# io-board-f-9.net
KiCad netlist of a schematic drawn in EAGLE
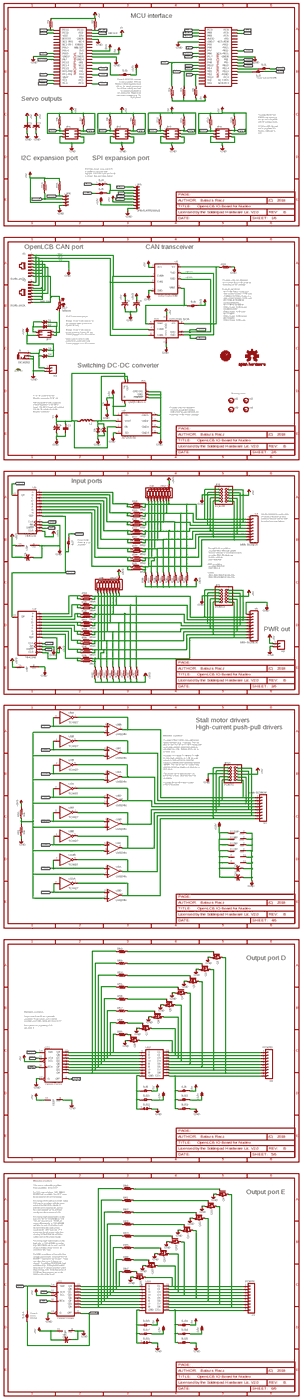
[diagram p0: schematic, sheet 1, overview]
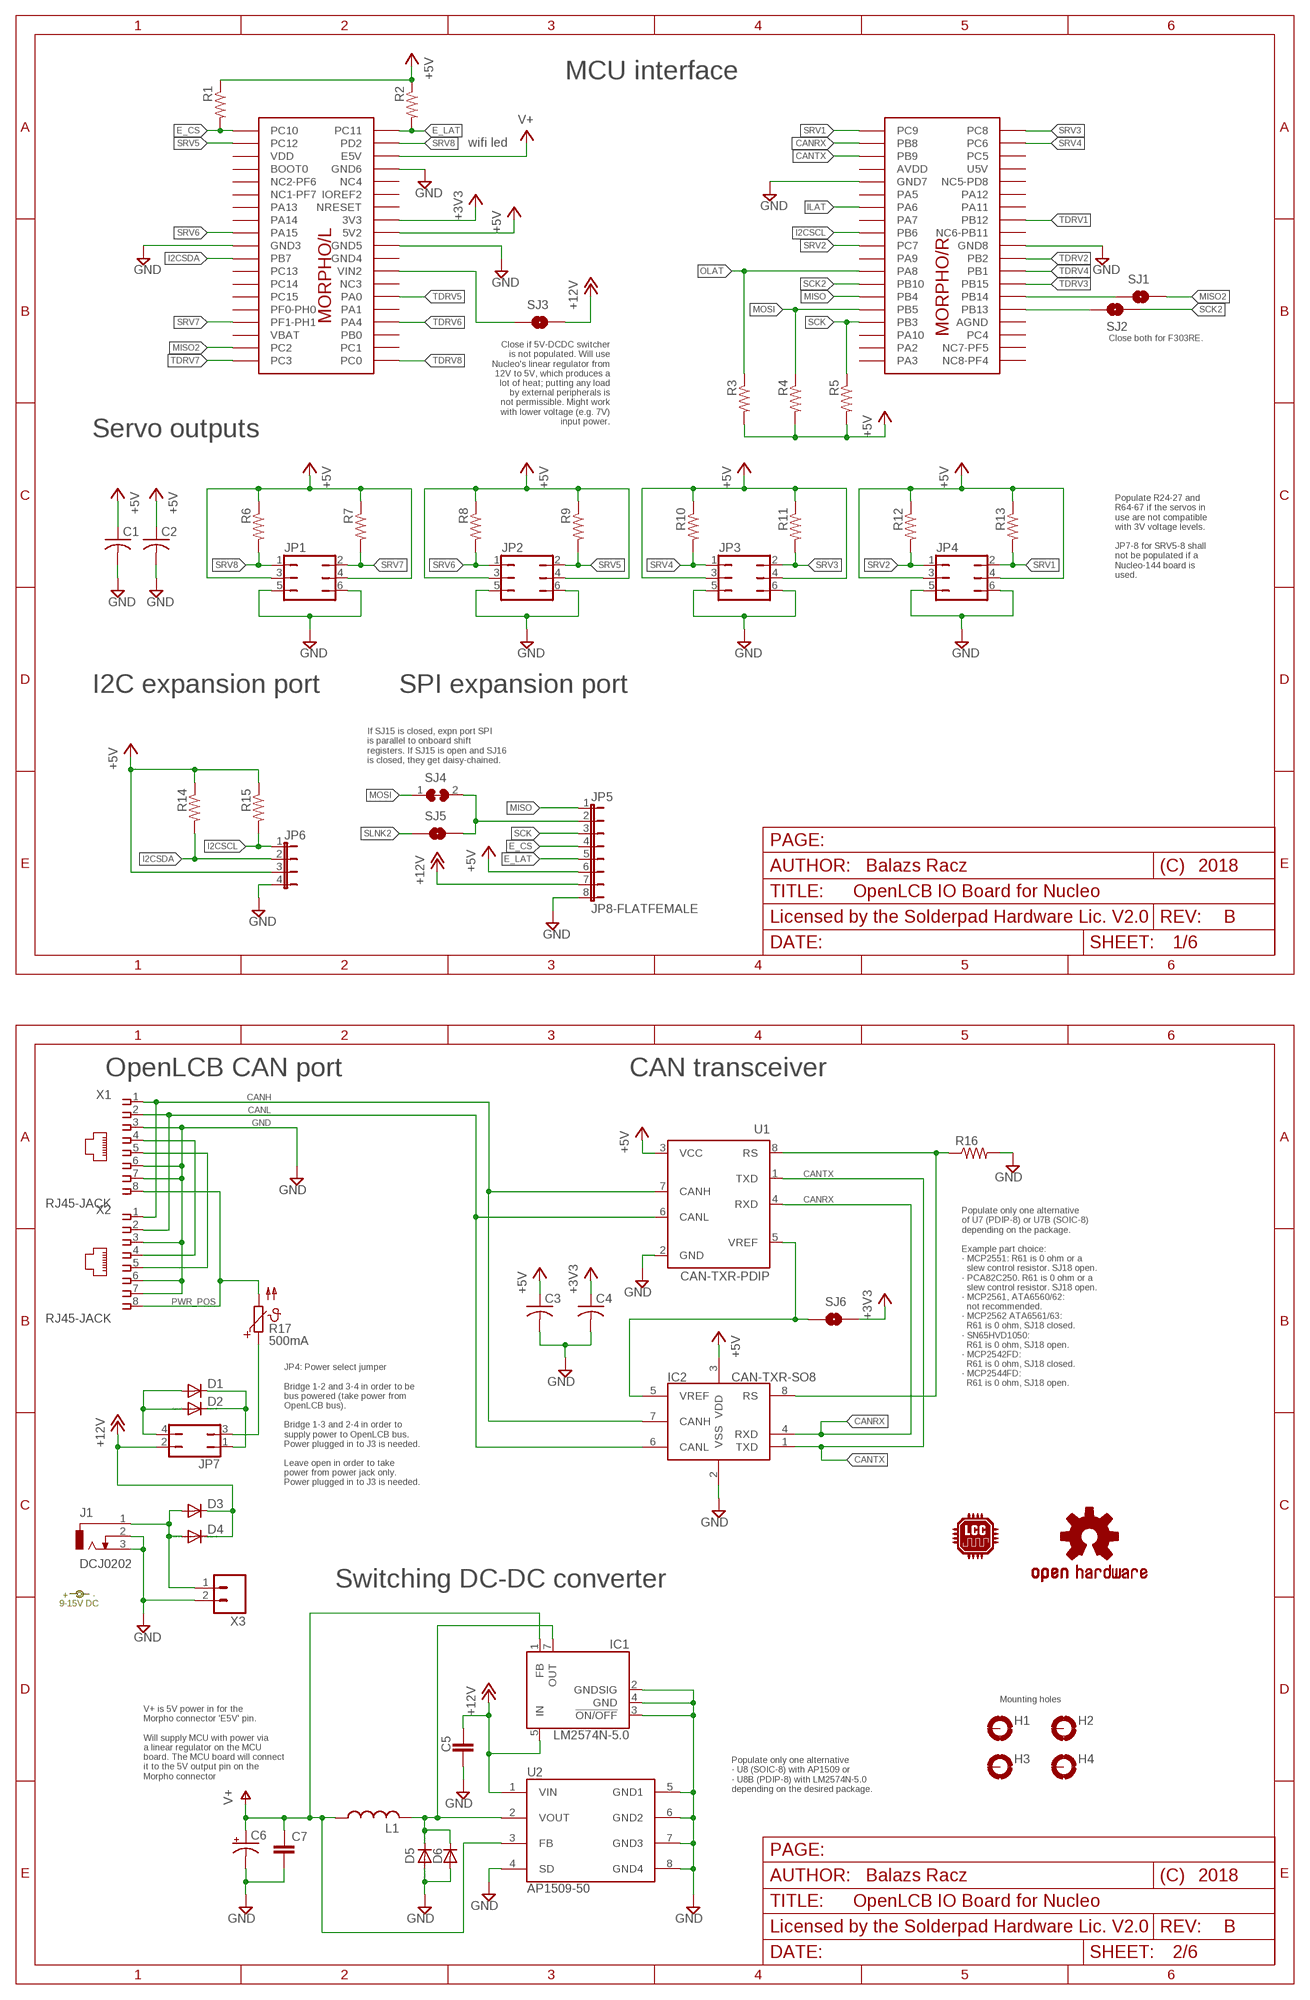
[diagram p1: schematic, sheet 1, part 1 of 4]
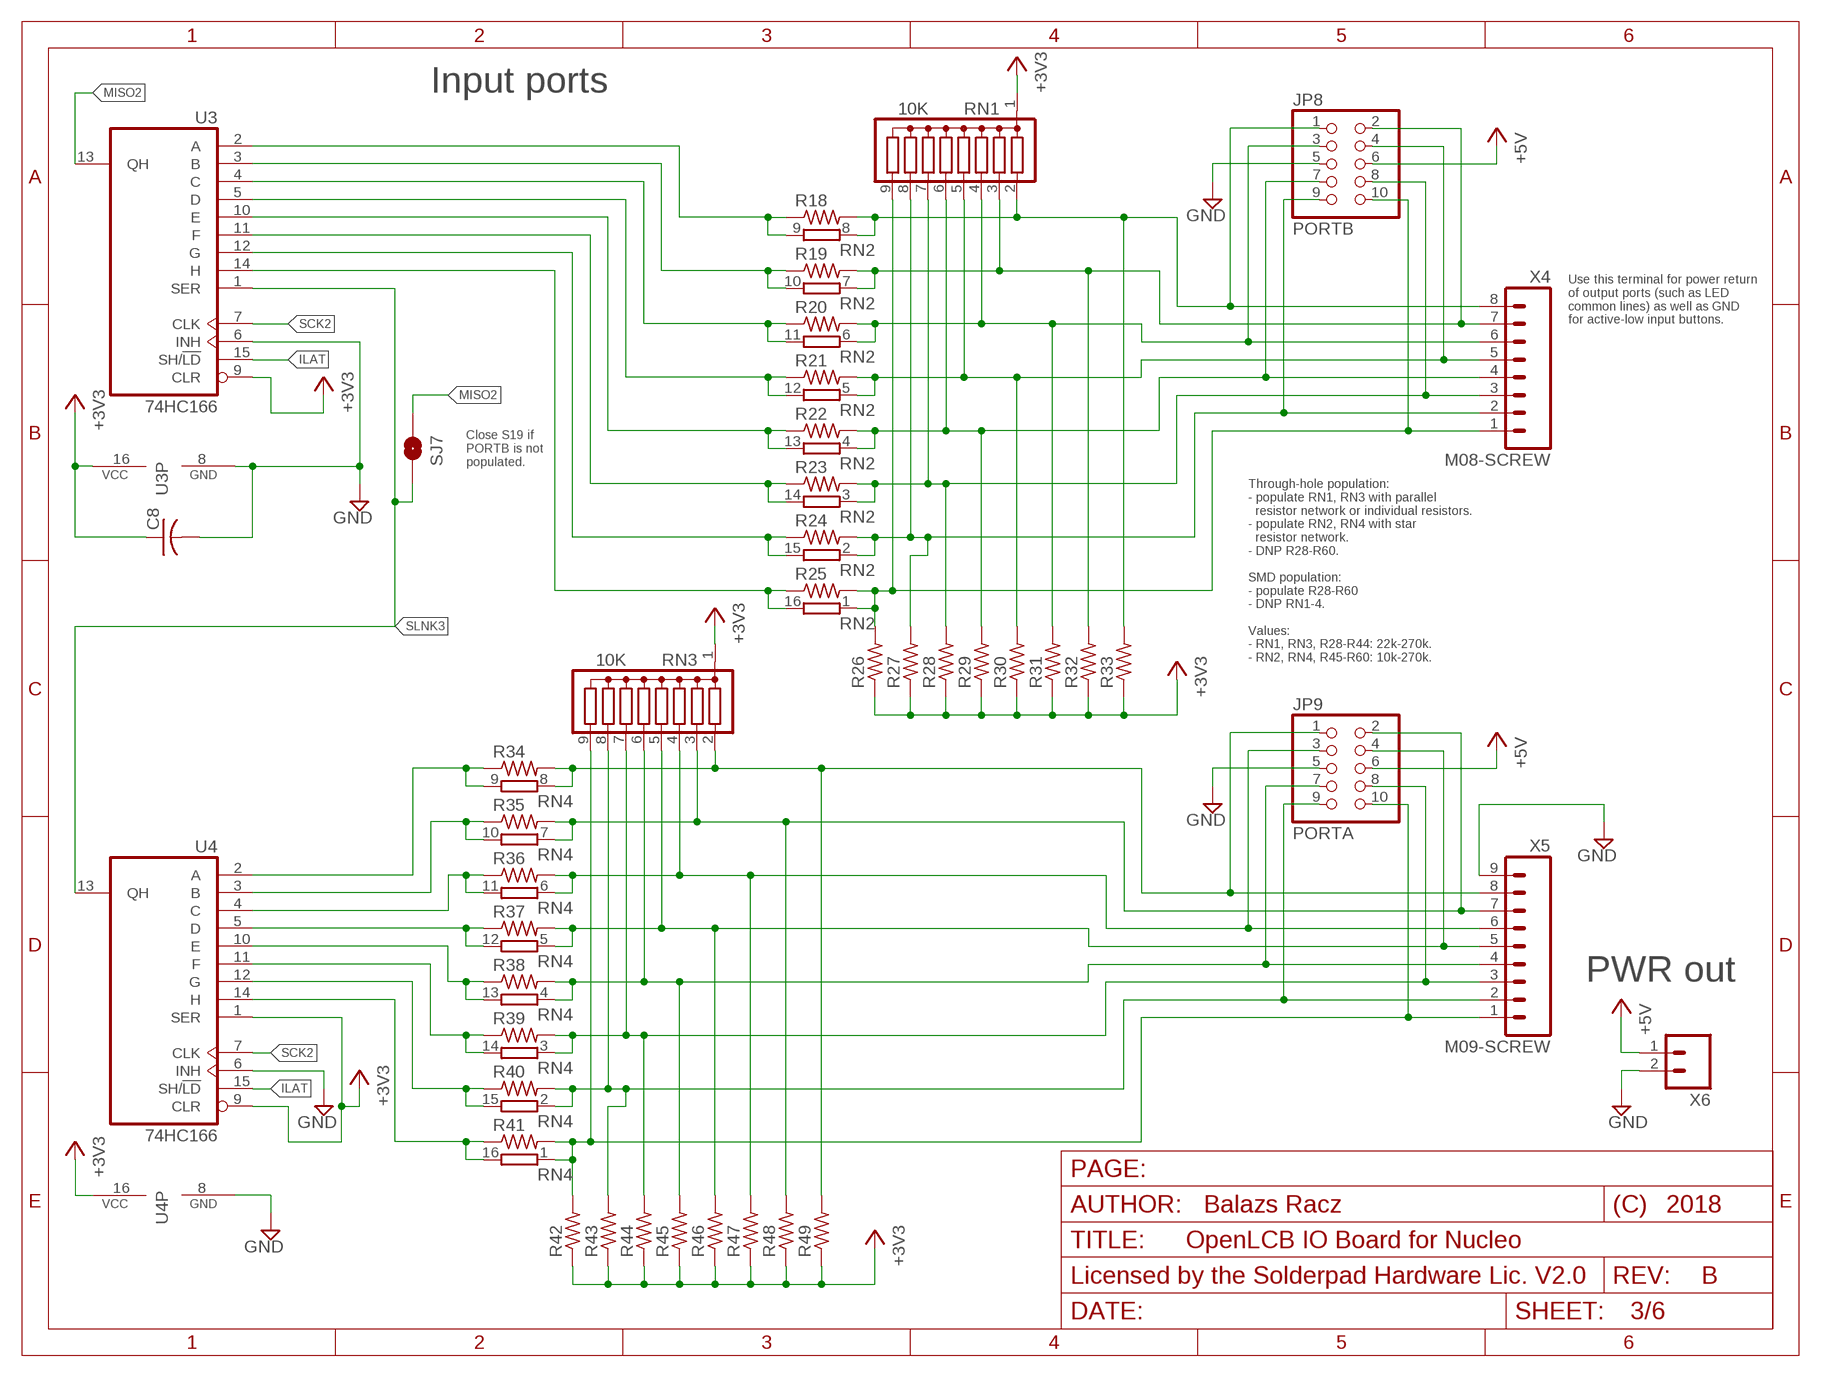
[diagram p2: schematic, sheet 1, part 2 of 4]
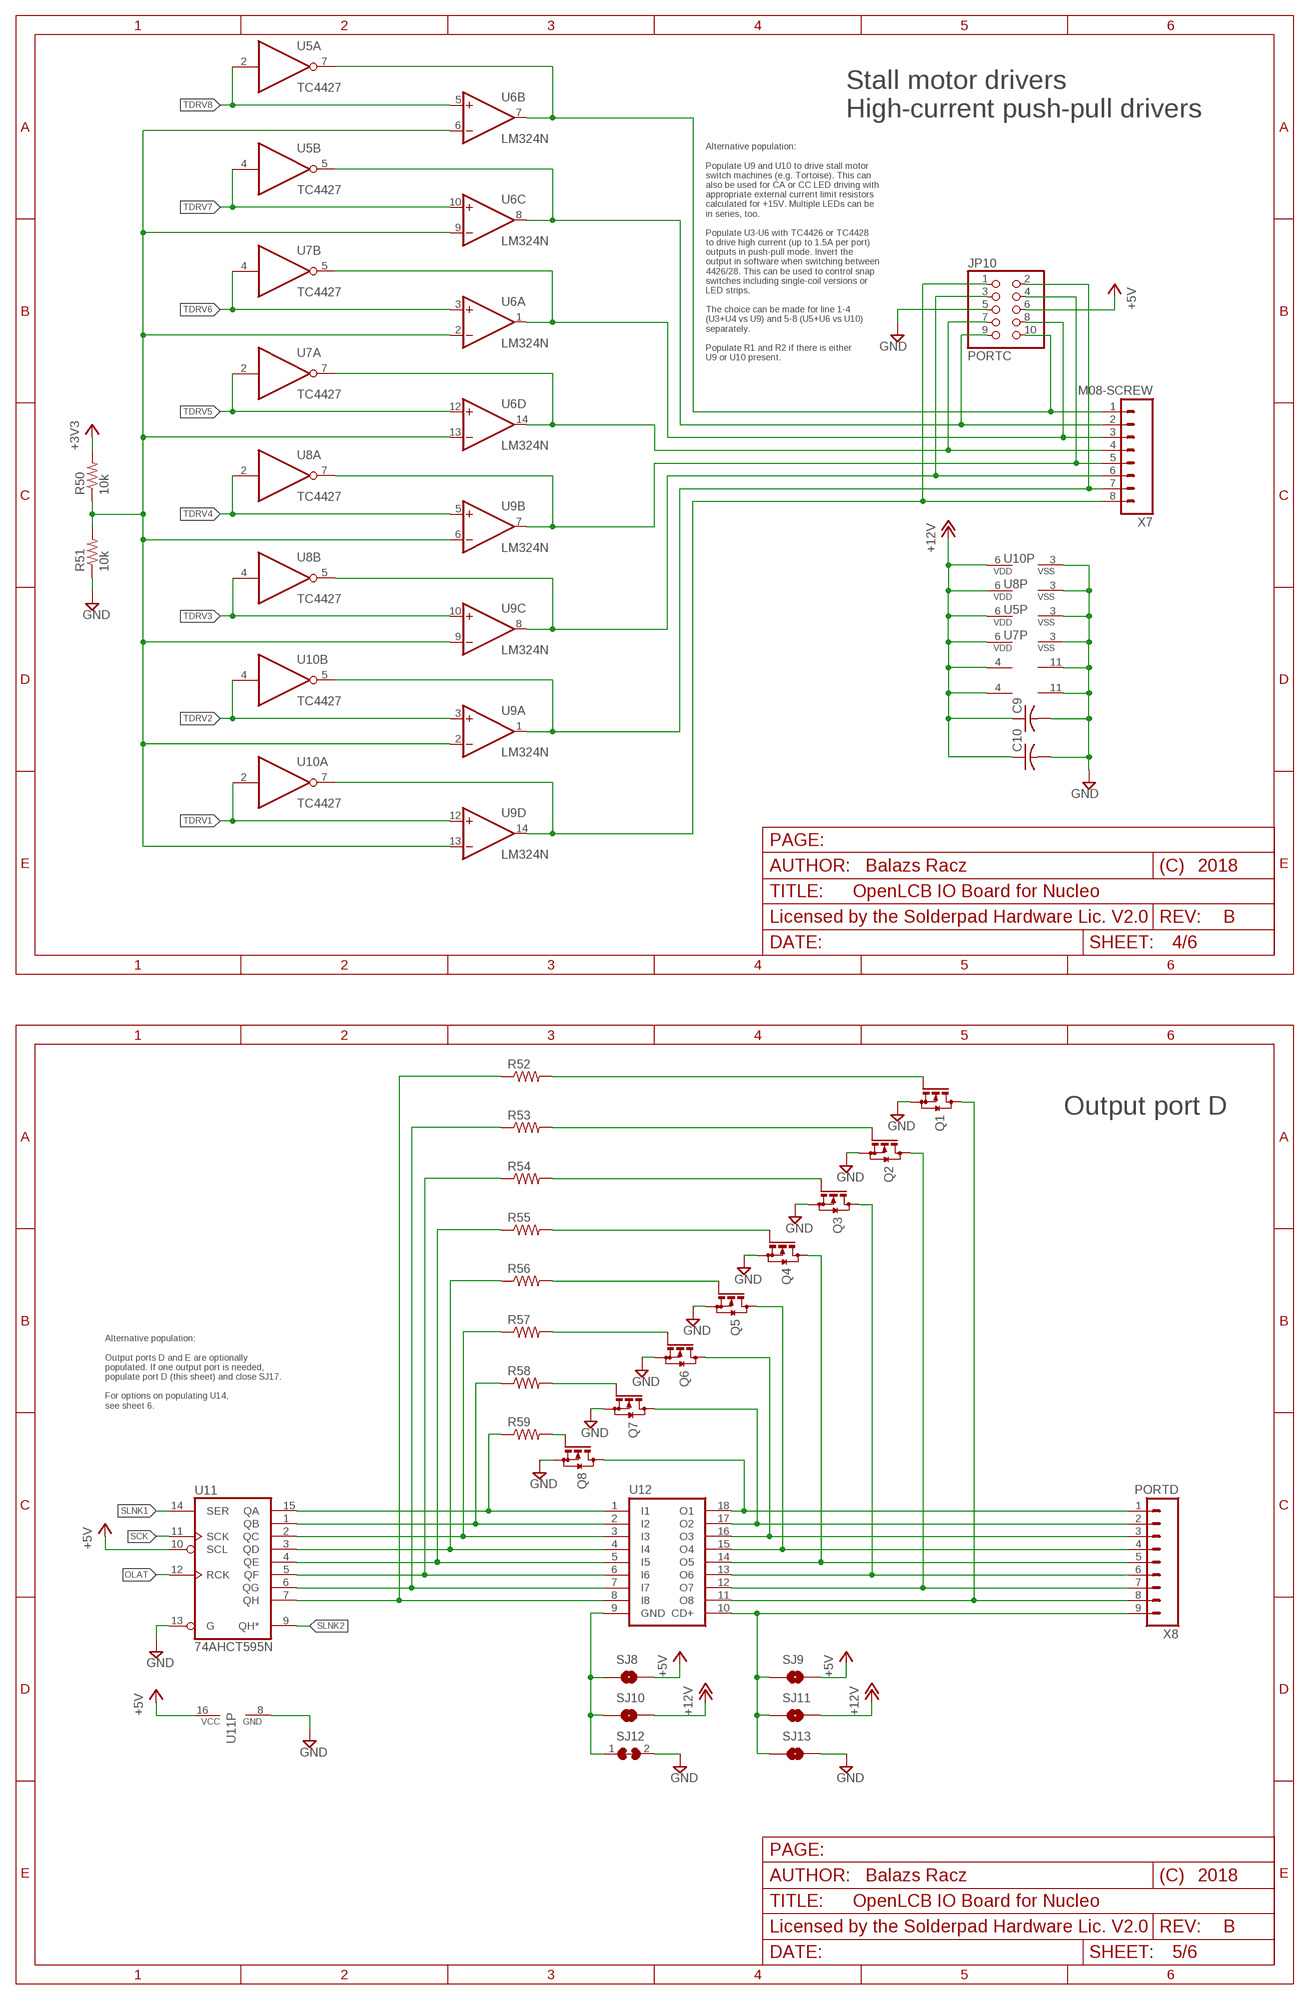
[diagram p3: schematic, sheet 1, part 3 of 4]
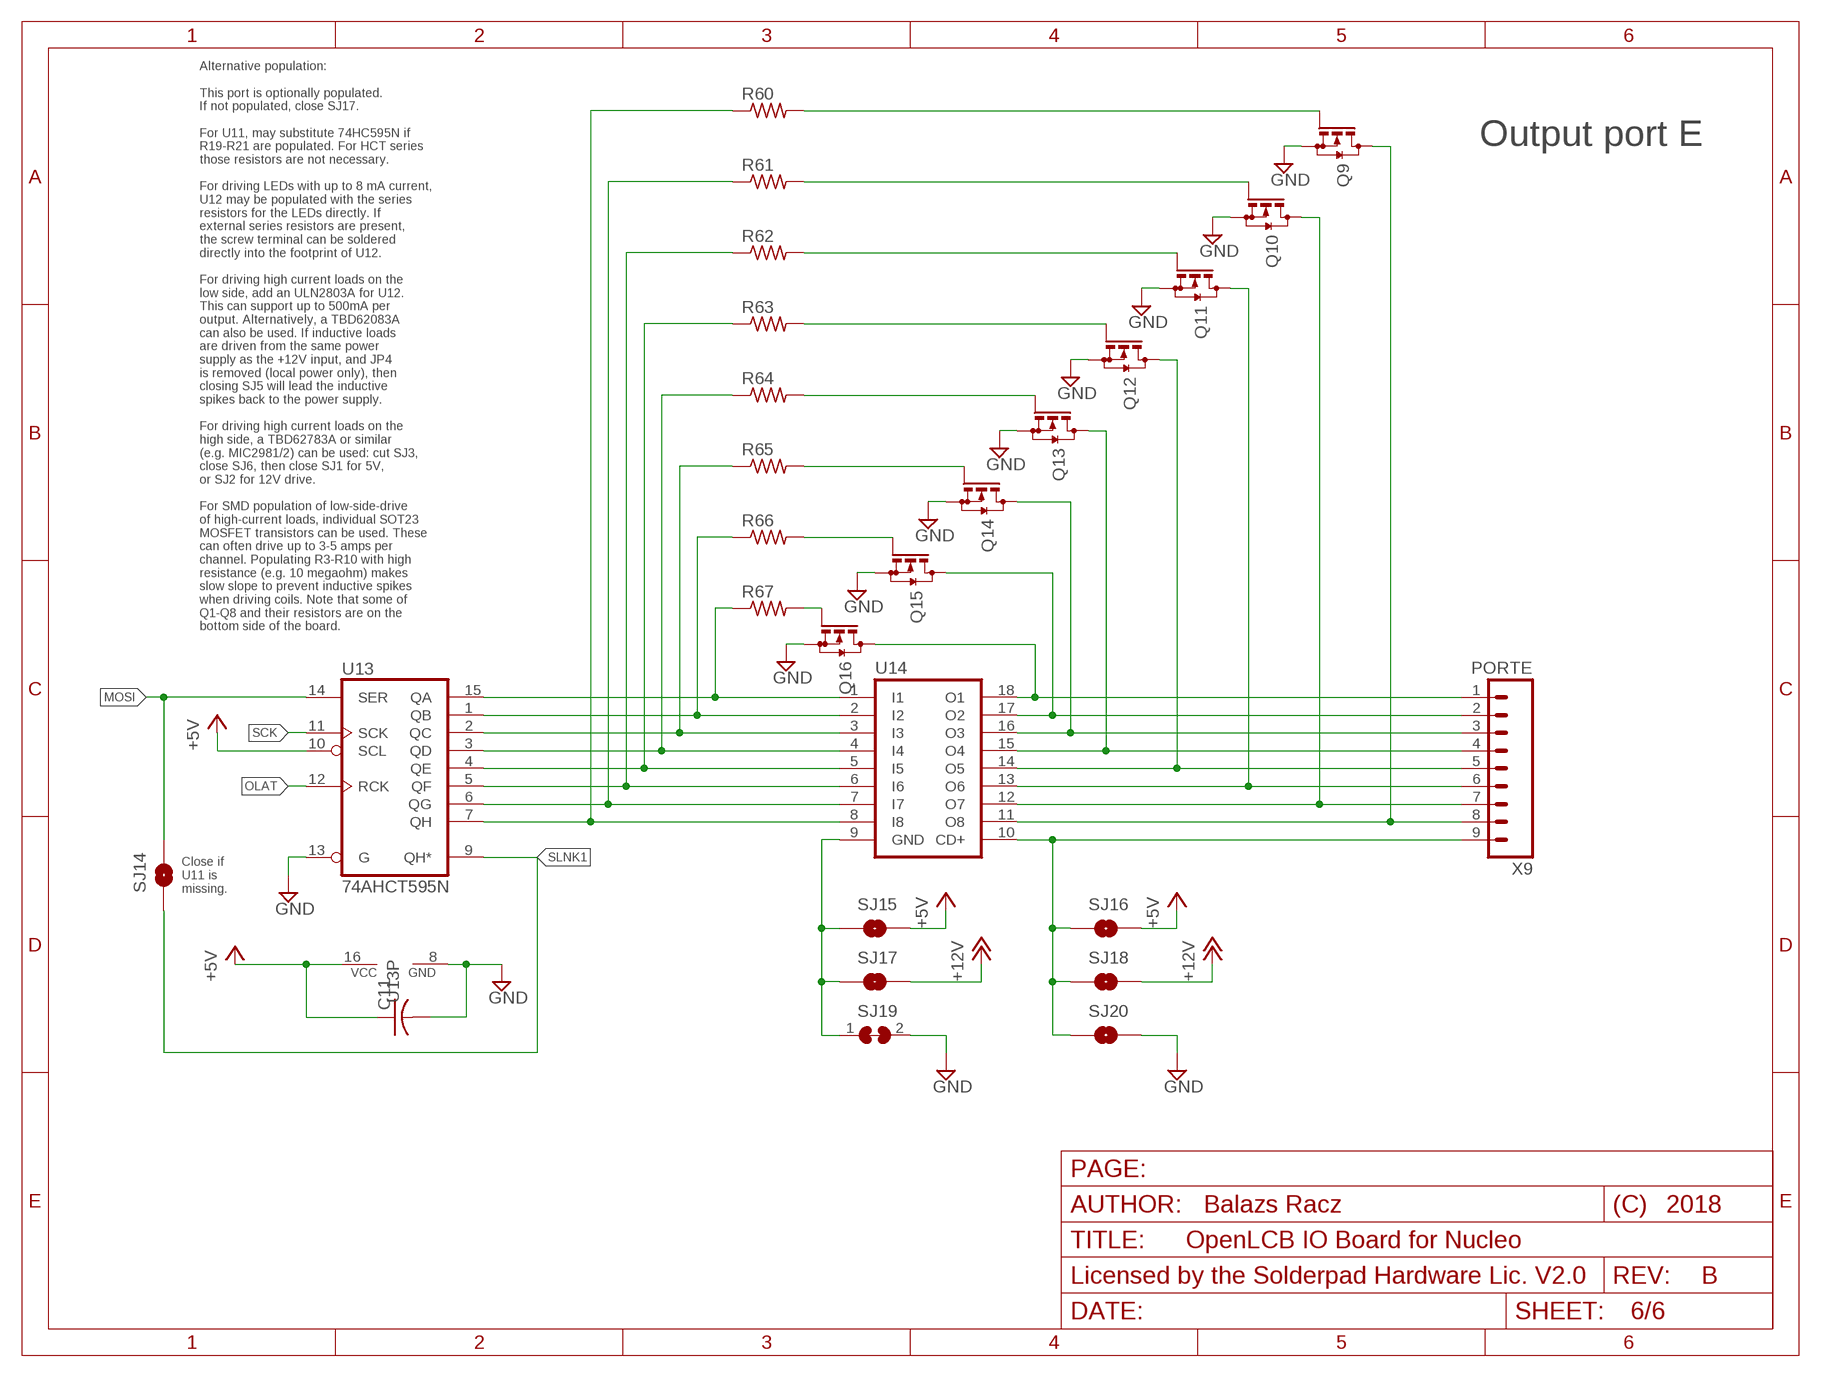
[diagram p4: schematic, sheet 1, part 4 of 4]

(export (version "E")
  (design (tool "Eeschema 10.0.6"))
  (components
    (comp (ref "C1")
      (value "C-USC1206")
      (footprint "eagle-import:C1206")
      (libsource (lib "eagle-import") (part "C-USC1206"))
    )
    (comp (ref "C2")
      (value "C-USC1206")
      (footprint "eagle-import:C1206")
      (libsource (lib "eagle-import") (part "C-USC1206"))
    )
    (comp (ref "C3")
      (value "C-USC0805")
      (footprint "eagle-import:C0805")
      (libsource (lib "eagle-import") (part "C-USC0805"))
    )
    (comp (ref "C4")
      (value "C-USC0805")
      (footprint "eagle-import:C0805")
      (libsource (lib "eagle-import") (part "C-USC0805"))
    )
    (comp (ref "C5")
      (value "C-EUC1206")
      (footprint "eagle-import:C1206")
      (libsource (lib "eagle-import") (part "C-EUC1206"))
    )
    (comp (ref "C6")
      (value "CPOL-USE2.5-5")
      (footprint "eagle-import:E2,5-5")
      (libsource (lib "eagle-import") (part "CPOL-USE2.5-5"))
    )
    (comp (ref "C7")
      (value "C-EUC1206")
      (footprint "eagle-import:C1206")
      (libsource (lib "eagle-import") (part "C-EUC1206"))
    )
    (comp (ref "C8")
      (value "C-USC0805")
      (footprint "eagle-import:C0805")
      (libsource (lib "eagle-import") (part "C-USC0805"))
    )
    (comp (ref "C9")
      (value "C-USC1206")
      (footprint "eagle-import:C1206")
      (libsource (lib "eagle-import") (part "C-USC1206"))
    )
    (comp (ref "C10")
      (value "C-USC1206")
      (footprint "eagle-import:C1206")
      (libsource (lib "eagle-import") (part "C-USC1206"))
    )
    (comp (ref "C11")
      (value "C-USC0805")
      (footprint "eagle-import:C0805")
      (libsource (lib "eagle-import") (part "C-USC0805"))
    )
    (comp (ref "D1")
      (value "DIODEDO-214AA-NODOC")
      (footprint "eagle-import:DO214AA-NODOC")
      (libsource (lib "eagle-import") (part "DIODEDO-214AA-NODOC"))
    )
    (comp (ref "D2")
      (value "DIODE-DO41-7.6")
      (footprint "eagle-import:DO41-7.6")
      (libsource (lib "eagle-import") (part "DIODE-DO41-7.6"))
    )
    (comp (ref "D3")
      (value "DIODEDO-214AA-NODOC")
      (footprint "eagle-import:DO214AA-NODOC")
      (libsource (lib "eagle-import") (part "DIODEDO-214AA-NODOC"))
    )
    (comp (ref "D4")
      (value "DIODE-DO41-7.6")
      (footprint "eagle-import:DO41-7.6")
      (libsource (lib "eagle-import") (part "DIODE-DO41-7.6"))
    )
    (comp (ref "D5")
      (value "DIODE-DO41-7.6")
      (footprint "eagle-import:DO41-7.6")
      (libsource (lib "eagle-import") (part "DIODE-DO41-7.6"))
    )
    (comp (ref "D6")
      (value "DIODEDO-214AA-NODOC")
      (footprint "eagle-import:DO214AA-NODOC")
      (libsource (lib "eagle-import") (part "DIODEDO-214AA-NODOC"))
    )
    (comp (ref "G1")
      (value "NUCLEO_64_GENERIC")
      (footprint "eagle-import:NUCLEO_BRD_BASE64")
      (libsource (lib "eagle-import") (part "NUCLEO_64_GENERIC"))
    )
    (comp (ref "H1")
      (value "MOUNT-PAD-ROUND3.3")
      (footprint "eagle-import:3,3-PAD")
      (libsource (lib "eagle-import") (part "MOUNT-PAD-ROUND3.3"))
    )
    (comp (ref "H2")
      (value "MOUNT-PAD-ROUND3.3")
      (footprint "eagle-import:3,3-PAD")
      (libsource (lib "eagle-import") (part "MOUNT-PAD-ROUND3.3"))
    )
    (comp (ref "H3")
      (value "MOUNT-PAD-ROUND3.3")
      (footprint "eagle-import:3,3-PAD")
      (libsource (lib "eagle-import") (part "MOUNT-PAD-ROUND3.3"))
    )
    (comp (ref "H4")
      (value "MOUNT-PAD-ROUND3.3")
      (footprint "eagle-import:3,3-PAD")
      (libsource (lib "eagle-import") (part "MOUNT-PAD-ROUND3.3"))
    )
    (comp (ref "IC1")
      (value "LM2574N-5.0")
      (footprint "eagle-import:DIL08")
      (libsource (lib "eagle-import") (part "LM2574?-N5.0"))
    )
    (comp (ref "IC2")
      (value "CAN-TXR-SO8")
      (footprint "eagle-import:SO-08")
      (libsource (lib "eagle-import") (part "MCP2551-SN"))
    )
    (comp (ref "J1")
      (value "DCJ0202")
      (footprint "eagle-import:DCJ0202")
      (libsource (lib "eagle-import") (part "DCJ0202"))
    )
    (comp (ref "JP1")
      (value "JP3Q")
      (footprint "eagle-import:JP3Q")
      (libsource (lib "eagle-import") (part "JP3Q"))
    )
    (comp (ref "JP2")
      (value "JP3Q")
      (footprint "eagle-import:JP3Q")
      (libsource (lib "eagle-import") (part "JP3Q"))
    )
    (comp (ref "JP3")
      (value "JP3Q")
      (footprint "eagle-import:JP3Q")
      (libsource (lib "eagle-import") (part "JP3Q"))
    )
    (comp (ref "JP4")
      (value "JP3Q")
      (footprint "eagle-import:JP3Q")
      (libsource (lib "eagle-import") (part "JP3Q"))
    )
    (comp (ref "JP5")
      (value "JP8-FLATFEMALE")
      (footprint "eagle-import:JP8F-FEM")
      (libsource (lib "eagle-import") (part "JP8-FLATFEMALE"))
    )
    (comp (ref "JP6")
      (value "JP4-FLAT")
      (footprint "eagle-import:JP4F")
      (libsource (lib "eagle-import") (part "JP4-FLAT"))
    )
    (comp (ref "JP7")
      (value "JP2Q")
      (footprint "eagle-import:JP2Q")
      (libsource (lib "eagle-import") (part "JP2Q"))
    )
    (comp (ref "JP8")
      (value "PORTB")
      (footprint "eagle-import:CON10M")
      (libsource (lib "eagle-import") (part "PINHD-2X5CN"))
    )
    (comp (ref "JP9")
      (value "PORTA")
      (footprint "eagle-import:CON10M")
      (libsource (lib "eagle-import") (part "PINHD-2X5CN"))
    )
    (comp (ref "JP10")
      (value "PORTC")
      (footprint "eagle-import:CON10M")
      (libsource (lib "eagle-import") (part "PINHD-2X5CN"))
    )
    (comp (ref "L1")
      (value "L-US")
      (footprint "eagle-import:L5-8,5")
      (libsource (lib "eagle-import") (part "L-US"))
    )
    (comp (ref "LG1")
      (value "LCC_LOGO")
      (footprint "eagle-import:LCC_LOGO")
      (libsource (lib "eagle-import") (part "LCC_LOGO"))
    )
    (comp (ref "LOGO1")
      (value "DOC-OSHW-LOGOM")
      (footprint "eagle-import:OSHW-LOGO-M")
      (libsource (lib "eagle-import") (part "DOC-OSHW-LOGOM"))
    )
    (comp (ref "P1")
      (value "9-15V DC")
      (footprint "eagle-import:POWER_USAGE")
      (libsource (lib "eagle-import") (part "DOC-POWER_LABEL"))
    )
    (comp (ref "Q1")
      (value "BSS123")
      (footprint "eagle-import:SOT23")
      (libsource (lib "eagle-import") (part "BSS123"))
    )
    (comp (ref "Q2")
      (value "BSS123")
      (footprint "eagle-import:SOT23")
      (libsource (lib "eagle-import") (part "BSS123"))
    )
    (comp (ref "Q3")
      (value "BSS123")
      (footprint "eagle-import:SOT23")
      (libsource (lib "eagle-import") (part "BSS123"))
    )
    (comp (ref "Q4")
      (value "BSS123")
      (footprint "eagle-import:SOT23")
      (libsource (lib "eagle-import") (part "BSS123"))
    )
    (comp (ref "Q5")
      (value "BSS123")
      (footprint "eagle-import:SOT23")
      (libsource (lib "eagle-import") (part "BSS123"))
    )
    (comp (ref "Q6")
      (value "BSS123")
      (footprint "eagle-import:SOT23")
      (libsource (lib "eagle-import") (part "BSS123"))
    )
    (comp (ref "Q7")
      (value "BSS123")
      (footprint "eagle-import:SOT23")
      (libsource (lib "eagle-import") (part "BSS123"))
    )
    (comp (ref "Q8")
      (value "BSS123")
      (footprint "eagle-import:SOT23")
      (libsource (lib "eagle-import") (part "BSS123"))
    )
    (comp (ref "Q9")
      (value "BSS123")
      (footprint "eagle-import:SOT23")
      (libsource (lib "eagle-import") (part "BSS123"))
    )
    (comp (ref "Q10")
      (value "BSS123")
      (footprint "eagle-import:SOT23")
      (libsource (lib "eagle-import") (part "BSS123"))
    )
    (comp (ref "Q11")
      (value "BSS123")
      (footprint "eagle-import:SOT23")
      (libsource (lib "eagle-import") (part "BSS123"))
    )
    (comp (ref "Q12")
      (value "BSS123")
      (footprint "eagle-import:SOT23")
      (libsource (lib "eagle-import") (part "BSS123"))
    )
    (comp (ref "Q13")
      (value "BSS123")
      (footprint "eagle-import:SOT23")
      (libsource (lib "eagle-import") (part "BSS123"))
    )
    (comp (ref "Q14")
      (value "BSS123")
      (footprint "eagle-import:SOT23")
      (libsource (lib "eagle-import") (part "BSS123"))
    )
    (comp (ref "Q15")
      (value "BSS123")
      (footprint "eagle-import:SOT23")
      (libsource (lib "eagle-import") (part "BSS123"))
    )
    (comp (ref "Q16")
      (value "BSS123")
      (footprint "eagle-import:SOT23")
      (libsource (lib "eagle-import") (part "BSS123"))
    )
    (comp (ref "R1")
      (value "R-US_R0805")
      (footprint "eagle-import:R0805")
      (libsource (lib "eagle-import") (part "rcl_334_R-US_R0805"))
    )
    (comp (ref "R2")
      (value "R-US_R0805")
      (footprint "eagle-import:R0805")
      (libsource (lib "eagle-import") (part "rcl_334_R-US_R0805"))
    )
    (comp (ref "R3")
      (value "R-US_R0805")
      (footprint "eagle-import:R0805")
      (libsource (lib "eagle-import") (part "rcl_334_R-US_R0805"))
    )
    (comp (ref "R4")
      (value "R-US_R0805")
      (footprint "eagle-import:R0805")
      (libsource (lib "eagle-import") (part "rcl_334_R-US_R0805"))
    )
    (comp (ref "R5")
      (value "R-US_R0805")
      (footprint "eagle-import:R0805")
      (libsource (lib "eagle-import") (part "rcl_334_R-US_R0805"))
    )
    (comp (ref "R6")
      (value "R-US_R0805")
      (footprint "eagle-import:R0805")
      (libsource (lib "eagle-import") (part "rcl_334_R-US_R0805"))
    )
    (comp (ref "R7")
      (value "R-US_R0805")
      (footprint "eagle-import:R0805")
      (libsource (lib "eagle-import") (part "rcl_334_R-US_R0805"))
    )
    (comp (ref "R8")
      (value "R-US_R0805")
      (footprint "eagle-import:R0805")
      (libsource (lib "eagle-import") (part "rcl_334_R-US_R0805"))
    )
    (comp (ref "R9")
      (value "R-US_R0805")
      (footprint "eagle-import:R0805")
      (libsource (lib "eagle-import") (part "rcl_334_R-US_R0805"))
    )
    (comp (ref "R10")
      (value "R-US_R0805")
      (footprint "eagle-import:R0805")
      (libsource (lib "eagle-import") (part "rcl_334_R-US_R0805"))
    )
    (comp (ref "R11")
      (value "R-US_R0805")
      (footprint "eagle-import:R0805")
      (libsource (lib "eagle-import") (part "rcl_334_R-US_R0805"))
    )
    (comp (ref "R12")
      (value "R-US_R0805")
      (footprint "eagle-import:R0805")
      (libsource (lib "eagle-import") (part "rcl_334_R-US_R0805"))
    )
    (comp (ref "R13")
      (value "R-US_R0805")
      (footprint "eagle-import:R0805")
      (libsource (lib "eagle-import") (part "rcl_334_R-US_R0805"))
    )
    (comp (ref "R14")
      (value "R-US_R0805")
      (footprint "eagle-import:R0805")
      (libsource (lib "eagle-import") (part "rcl_334_R-US_R0805"))
    )
    (comp (ref "R15")
      (value "R-US_R0805")
      (footprint "eagle-import:R0805")
      (libsource (lib "eagle-import") (part "rcl_334_R-US_R0805"))
    )
    (comp (ref "R16")
      (value "R-US_R0805")
      (footprint "eagle-import:R0805")
      (libsource (lib "eagle-import") (part "rcl_334_R-US_R0805"))
    )
    (comp (ref "R17")
      (value "500mA")
      (footprint "eagle-import:PTC1812")
      (libsource (lib "eagle-import") (part "PTC_1812"))
    )
    (comp (ref "R18")
      (value "R-US_R0603")
      (footprint "eagle-import:R0603")
      (libsource (lib "eagle-import") (part "rcl_334_R-US_R0603"))
    )
    (comp (ref "R19")
      (value "R-US_R0603")
      (footprint "eagle-import:R0603")
      (libsource (lib "eagle-import") (part "rcl_334_R-US_R0603"))
    )
    (comp (ref "R20")
      (value "R-US_R0603")
      (footprint "eagle-import:R0603")
      (libsource (lib "eagle-import") (part "rcl_334_R-US_R0603"))
    )
    (comp (ref "R21")
      (value "R-US_R0603")
      (footprint "eagle-import:R0603")
      (libsource (lib "eagle-import") (part "rcl_334_R-US_R0603"))
    )
    (comp (ref "R22")
      (value "R-US_R0603")
      (footprint "eagle-import:R0603")
      (libsource (lib "eagle-import") (part "rcl_334_R-US_R0603"))
    )
    (comp (ref "R23")
      (value "R-US_R0603")
      (footprint "eagle-import:R0603")
      (libsource (lib "eagle-import") (part "rcl_334_R-US_R0603"))
    )
    (comp (ref "R24")
      (value "R-US_R0603")
      (footprint "eagle-import:R0603")
      (libsource (lib "eagle-import") (part "rcl_334_R-US_R0603"))
    )
    (comp (ref "R25")
      (value "R-US_R0603")
      (footprint "eagle-import:R0603")
      (libsource (lib "eagle-import") (part "rcl_334_R-US_R0603"))
    )
    (comp (ref "R26")
      (value "R-US")
      (footprint "eagle-import:R0603")
      (libsource (lib "eagle-import") (part "R-US"))
    )
    (comp (ref "R27")
      (value "R-US")
      (footprint "eagle-import:R0603")
      (libsource (lib "eagle-import") (part "R-US"))
    )
    (comp (ref "R28")
      (value "R-US")
      (footprint "eagle-import:R0603")
      (libsource (lib "eagle-import") (part "R-US"))
    )
    (comp (ref "R29")
      (value "R-US")
      (footprint "eagle-import:R0603")
      (libsource (lib "eagle-import") (part "R-US"))
    )
    (comp (ref "R30")
      (value "R-US")
      (footprint "eagle-import:R0603")
      (libsource (lib "eagle-import") (part "R-US"))
    )
    (comp (ref "R31")
      (value "R-US")
      (footprint "eagle-import:R0603")
      (libsource (lib "eagle-import") (part "R-US"))
    )
    (comp (ref "R32")
      (value "R-US")
      (footprint "eagle-import:R0603")
      (libsource (lib "eagle-import") (part "R-US"))
    )
    (comp (ref "R33")
      (value "R-US")
      (footprint "eagle-import:R0603")
      (libsource (lib "eagle-import") (part "R-US"))
    )
    (comp (ref "R34")
      (value "R-US_R0603")
      (footprint "eagle-import:R0603")
      (libsource (lib "eagle-import") (part "rcl_334_R-US_R0603"))
    )
    (comp (ref "R35")
      (value "R-US_R0603")
      (footprint "eagle-import:R0603")
      (libsource (lib "eagle-import") (part "rcl_334_R-US_R0603"))
    )
    (comp (ref "R36")
      (value "R-US_R0603")
      (footprint "eagle-import:R0603")
      (libsource (lib "eagle-import") (part "rcl_334_R-US_R0603"))
    )
    (comp (ref "R37")
      (value "R-US_R0603")
      (footprint "eagle-import:R0603")
      (libsource (lib "eagle-import") (part "rcl_334_R-US_R0603"))
    )
    (comp (ref "R38")
      (value "R-US_R0603")
      (footprint "eagle-import:R0603")
      (libsource (lib "eagle-import") (part "rcl_334_R-US_R0603"))
    )
    (comp (ref "R39")
      (value "R-US_R0603")
      (footprint "eagle-import:R0603")
      (libsource (lib "eagle-import") (part "rcl_334_R-US_R0603"))
    )
    (comp (ref "R40")
      (value "R-US_R0603")
      (footprint "eagle-import:R0603")
      (libsource (lib "eagle-import") (part "rcl_334_R-US_R0603"))
    )
    (comp (ref "R41")
      (value "R-US_R0603")
      (footprint "eagle-import:R0603")
      (libsource (lib "eagle-import") (part "rcl_334_R-US_R0603"))
    )
    (comp (ref "R42")
      (value "R-US")
      (footprint "eagle-import:R0603")
      (libsource (lib "eagle-import") (part "R-US"))
    )
    (comp (ref "R43")
      (value "R-US")
      (footprint "eagle-import:R0603")
      (libsource (lib "eagle-import") (part "R-US"))
    )
    (comp (ref "R44")
      (value "R-US")
      (footprint "eagle-import:R0603")
      (libsource (lib "eagle-import") (part "R-US"))
    )
    (comp (ref "R45")
      (value "R-US")
      (footprint "eagle-import:R0603")
      (libsource (lib "eagle-import") (part "R-US"))
    )
    (comp (ref "R46")
      (value "R-US")
      (footprint "eagle-import:R0603")
      (libsource (lib "eagle-import") (part "R-US"))
    )
    (comp (ref "R47")
      (value "R-US")
      (footprint "eagle-import:R0603")
      (libsource (lib "eagle-import") (part "R-US"))
    )
    (comp (ref "R48")
      (value "R-US")
      (footprint "eagle-import:R0603")
      (libsource (lib "eagle-import") (part "R-US"))
    )
    (comp (ref "R49")
      (value "R-US")
      (footprint "eagle-import:R0603")
      (libsource (lib "eagle-import") (part "R-US"))
    )
    (comp (ref "R50")
      (value "10k")
      (footprint "eagle-import:R0805")
      (libsource (lib "eagle-import") (part "R-US_R0805"))
    )
    (comp (ref "R51")
      (value "10k")
      (footprint "eagle-import:R0805")
      (libsource (lib "eagle-import") (part "R-US_R0805"))
    )
    (comp (ref "R52")
      (value "R-US_R0603")
      (footprint "eagle-import:R0603")
      (libsource (lib "eagle-import") (part "R-US_R0603"))
    )
    (comp (ref "R53")
      (value "R-US_R0603")
      (footprint "eagle-import:R0603")
      (libsource (lib "eagle-import") (part "R-US_R0603"))
    )
    (comp (ref "R54")
      (value "R-US_R0603")
      (footprint "eagle-import:R0603")
      (libsource (lib "eagle-import") (part "R-US_R0603"))
    )
    (comp (ref "R55")
      (value "R-US_R0603")
      (footprint "eagle-import:R0603")
      (libsource (lib "eagle-import") (part "R-US_R0603"))
    )
    (comp (ref "R56")
      (value "R-US_R0603")
      (footprint "eagle-import:R0603")
      (libsource (lib "eagle-import") (part "R-US_R0603"))
    )
    (comp (ref "R57")
      (value "R-US_R0603")
      (footprint "eagle-import:R0603")
      (libsource (lib "eagle-import") (part "R-US_R0603"))
    )
    (comp (ref "R58")
      (value "R-US_R0603")
      (footprint "eagle-import:R0603")
      (libsource (lib "eagle-import") (part "R-US_R0603"))
    )
    (comp (ref "R59")
      (value "R-US_R0603")
      (footprint "eagle-import:R0603")
      (libsource (lib "eagle-import") (part "R-US_R0603"))
    )
    (comp (ref "R60")
      (value "R-US_R0603")
      (footprint "eagle-import:R0603")
      (libsource (lib "eagle-import") (part "R-US_R0603"))
    )
    (comp (ref "R61")
      (value "R-US_R0603")
      (footprint "eagle-import:R0603")
      (libsource (lib "eagle-import") (part "R-US_R0603"))
    )
    (comp (ref "R62")
      (value "R-US_R0603")
      (footprint "eagle-import:R0603")
      (libsource (lib "eagle-import") (part "R-US_R0603"))
    )
    (comp (ref "R63")
      (value "R-US_R0603")
      (footprint "eagle-import:R0603")
      (libsource (lib "eagle-import") (part "R-US_R0603"))
    )
    (comp (ref "R64")
      (value "R-US_R0603")
      (footprint "eagle-import:R0603")
      (libsource (lib "eagle-import") (part "R-US_R0603"))
    )
    (comp (ref "R65")
      (value "R-US_R0603")
      (footprint "eagle-import:R0603")
      (libsource (lib "eagle-import") (part "R-US_R0603"))
    )
    (comp (ref "R66")
      (value "R-US_R0603")
      (footprint "eagle-import:R0603")
      (libsource (lib "eagle-import") (part "R-US_R0603"))
    )
    (comp (ref "R67")
      (value "R-US_R0603")
      (footprint "eagle-import:R0603")
      (libsource (lib "eagle-import") (part "R-US_R0603"))
    )
    (comp (ref "RN1")
      (value "10K")
      (footprint "eagle-import:SIL9")
      (libsource (lib "eagle-import") (part "G08R"))
    )
    (comp (ref "RN2")
      (value "8R-P")
      (footprint "eagle-import:DIL16")
      (libsource (lib "eagle-import") (part "8R-P"))
    )
    (comp (ref "RN3")
      (value "10K")
      (footprint "eagle-import:SIL9")
      (libsource (lib "eagle-import") (part "G08R"))
    )
    (comp (ref "RN4")
      (value "8R-P")
      (footprint "eagle-import:DIL16")
      (libsource (lib "eagle-import") (part "8R-P"))
    )
    (comp (ref "SJ1")
      (value "SJRND2")
      (footprint "eagle-import:SJ_RND2")
      (libsource (lib "eagle-import") (part "SJRND2"))
    )
    (comp (ref "SJ2")
      (value "SJRND2")
      (footprint "eagle-import:SJ_RND2")
      (libsource (lib "eagle-import") (part "SJRND2"))
    )
    (comp (ref "SJ3")
      (value "SJRND2")
      (footprint "eagle-import:SJ_RND2")
      (libsource (lib "eagle-import") (part "SJRND2"))
    )
    (comp (ref "SJ4")
      (value "SJ-C")
      (footprint "eagle-import:SJW-C")
      (libsource (lib "eagle-import") (part "SJ-C"))
    )
    (comp (ref "SJ5")
      (value "SJRND2")
      (footprint "eagle-import:SJ_RND2")
      (libsource (lib "eagle-import") (part "SJRND2"))
    )
    (comp (ref "SJ6")
      (value "SJRND2")
      (footprint "eagle-import:SJ_RND2")
      (libsource (lib "eagle-import") (part "SJRND2"))
    )
    (comp (ref "SJ7")
      (value "SJRND2")
      (footprint "eagle-import:SJ_RND2")
      (libsource (lib "eagle-import") (part "SJRND2"))
    )
    (comp (ref "SJ8")
      (value "SJRND2")
      (footprint "eagle-import:SJ_RND2")
      (libsource (lib "eagle-import") (part "SJRND2"))
    )
    (comp (ref "SJ9")
      (value "SJRND2")
      (footprint "eagle-import:SJ_RND2")
      (libsource (lib "eagle-import") (part "SJRND2"))
    )
    (comp (ref "SJ10")
      (value "SJRND2")
      (footprint "eagle-import:SJ_RND2")
      (libsource (lib "eagle-import") (part "SJRND2"))
    )
    (comp (ref "SJ11")
      (value "SJRND2")
      (footprint "eagle-import:SJ_RND2")
      (libsource (lib "eagle-import") (part "SJRND2"))
    )
    (comp (ref "SJ12")
      (value "SJ-C")
      (footprint "eagle-import:SJW-C")
      (libsource (lib "eagle-import") (part "SJ-C"))
    )
    (comp (ref "SJ13")
      (value "SJRND2")
      (footprint "eagle-import:SJ_RND2")
      (libsource (lib "eagle-import") (part "SJRND2"))
    )
    (comp (ref "SJ14")
      (value "SJRND2")
      (footprint "eagle-import:SJ_RND2")
      (libsource (lib "eagle-import") (part "SJRND2"))
    )
    (comp (ref "SJ15")
      (value "SJRND2")
      (footprint "eagle-import:SJ_RND2")
      (libsource (lib "eagle-import") (part "SJRND2"))
    )
    (comp (ref "SJ16")
      (value "SJRND2")
      (footprint "eagle-import:SJ_RND2")
      (libsource (lib "eagle-import") (part "SJRND2"))
    )
    (comp (ref "SJ17")
      (value "SJRND2")
      (footprint "eagle-import:SJ_RND2")
      (libsource (lib "eagle-import") (part "SJRND2"))
    )
    (comp (ref "SJ18")
      (value "SJRND2")
      (footprint "eagle-import:SJ_RND2")
      (libsource (lib "eagle-import") (part "SJRND2"))
    )
    (comp (ref "SJ19")
      (value "SJ-C")
      (footprint "eagle-import:SJW-C")
      (libsource (lib "eagle-import") (part "SJ-C"))
    )
    (comp (ref "SJ20")
      (value "SJRND2")
      (footprint "eagle-import:SJ_RND2")
      (libsource (lib "eagle-import") (part "SJRND2"))
    )
    (comp (ref "U1")
      (value "CAN-TXR-PDIP")
      (footprint "eagle-import:DIL08")
      (libsource (lib "eagle-import") (part "PCA82C250"))
    )
    (comp (ref "U2")
      (value "AP1509-50")
      (footprint "eagle-import:SO-08")
      (libsource (lib "eagle-import") (part "AP1509"))
    )
    (comp (ref "U3")
      (value "74HC166")
      (footprint "eagle-import:DIL16")
      (libsource (lib "eagle-import") (part "74166N"))
    )
    (comp (ref "U4")
      (value "74HC166")
      (footprint "eagle-import:DIL16")
      (libsource (lib "eagle-import") (part "74166N"))
    )
    (comp (ref "U5")
      (value "TC4427")
      (footprint "eagle-import:DIL08-LONG")
      (libsource (lib "eagle-import") (part "TC4426APDIP"))
    )
    (comp (ref "U6")
      (value "LM324N")
      (footprint "eagle-import:DIL14")
      (libsource (lib "eagle-import") (part "LM324N"))
    )
    (comp (ref "U7")
      (value "TC4427")
      (footprint "eagle-import:DIL08-LONG")
      (libsource (lib "eagle-import") (part "TC4426APDIP"))
    )
    (comp (ref "U8")
      (value "TC4427")
      (footprint "eagle-import:DIL08-LONG")
      (libsource (lib "eagle-import") (part "TC4426APDIP"))
    )
    (comp (ref "U9")
      (value "LM324N")
      (footprint "eagle-import:DIL14")
      (libsource (lib "eagle-import") (part "LM324N"))
    )
    (comp (ref "U10")
      (value "TC4427")
      (footprint "eagle-import:DIL08-LONG")
      (libsource (lib "eagle-import") (part "TC4426APDIP"))
    )
    (comp (ref "U11")
      (value "74AHCT595N")
      (footprint "eagle-import:DIL16")
      (libsource (lib "eagle-import") (part "74595NHCT"))
    )
    (comp (ref "U12")
      (value "ULN2803A")
      (footprint "eagle-import:DIL18-THIN")
      (libsource (lib "eagle-import") (part "ULN2803A"))
    )
    (comp (ref "U13")
      (value "74AHCT595N")
      (footprint "eagle-import:DIL16")
      (libsource (lib "eagle-import") (part "74595NHCT"))
    )
    (comp (ref "U14")
      (value "ULN2803A")
      (footprint "eagle-import:DIL18-THIN")
      (libsource (lib "eagle-import") (part "ULN2803A"))
    )
    (comp (ref "X1")
      (value "RJ45-JACK")
      (footprint "eagle-import:RJ45-PULSE-E5J88")
      (libsource (lib "eagle-import") (part "RJ45-JACKRJ45-PULSE-E5J00"))
    )
    (comp (ref "X2")
      (value "RJ45-JACK")
      (footprint "eagle-import:RJ45-PULSE-E5J88")
      (libsource (lib "eagle-import") (part "RJ45-JACKRJ45-PULSE-E5J00"))
    )
    (comp (ref "X3")
      (value "CONNECTOR-M023.5MM-LOCK")
      (footprint "eagle-import:SCREWTERMINAL-3.5MM-2_LOCK")
      (libsource (lib "eagle-import") (part "CONNECTOR-M023.5MM-LOCK"))
    )
    (comp (ref "X4")
      (value "M08-SCREW")
      (footprint "eagle-import:1X08_TERMINAL")
      (libsource (lib "eagle-import") (part "M08-SCREW"))
    )
    (comp (ref "X5")
      (value "M09-SCREW")
      (footprint "eagle-import:1X09_TERMINAL")
      (libsource (lib "eagle-import") (part "M09-SCREW"))
    )
    (comp (ref "X6")
      (value "CONNECTOR-M023.5MM-LOCK")
      (footprint "eagle-import:SCREWTERMINAL-3.5MM-2_LOCK")
      (libsource (lib "eagle-import") (part "CONNECTOR-M023.5MM-LOCK"))
    )
    (comp (ref "X7")
      (value "M08-SCREW")
      (footprint "eagle-import:1X08_TERMINAL")
      (libsource (lib "eagle-import") (part "M08-SCREW"))
    )
    (comp (ref "X8")
      (value "PORTD")
      (footprint "eagle-import:1X09_TERMINAL")
      (libsource (lib "eagle-import") (part "M09-SCREW"))
    )
    (comp (ref "X9")
      (value "PORTE")
      (footprint "eagle-import:1X09_TERMINAL")
      (libsource (lib "eagle-import") (part "M09-SCREW"))
    )
  )
  (nets
    (net (code "1") (name "+3V3") (class "Default")
      (node (ref "C4") (pin "1") (pinfunction "1_1") (pintype "passive"))
      (node (ref "C8") (pin "1") (pinfunction "1_1") (pintype "passive"))
      (node (ref "G1") (pin "3V3") (pinfunction "3V3_3V3") (pintype "power_in"))
      (node (ref "R26") (pin "1") (pinfunction "1_1") (pintype "passive"))
      (node (ref "R27") (pin "1") (pinfunction "1_1") (pintype "passive"))
      (node (ref "R28") (pin "1") (pinfunction "1_1") (pintype "passive"))
      (node (ref "R29") (pin "1") (pinfunction "1_1") (pintype "passive"))
      (node (ref "R30") (pin "1") (pinfunction "1_1") (pintype "passive"))
      (node (ref "R31") (pin "1") (pinfunction "1_1") (pintype "passive"))
      (node (ref "R32") (pin "1") (pinfunction "1_1") (pintype "passive"))
      (node (ref "R33") (pin "1") (pinfunction "1_1") (pintype "passive"))
      (node (ref "R42") (pin "1") (pinfunction "1_1") (pintype "passive"))
      (node (ref "R43") (pin "1") (pinfunction "1_1") (pintype "passive"))
      (node (ref "R44") (pin "1") (pinfunction "1_1") (pintype "passive"))
      (node (ref "R45") (pin "1") (pinfunction "1_1") (pintype "passive"))
      (node (ref "R46") (pin "1") (pinfunction "1_1") (pintype "passive"))
      (node (ref "R47") (pin "1") (pinfunction "1_1") (pintype "passive"))
      (node (ref "R48") (pin "1") (pinfunction "1_1") (pintype "passive"))
      (node (ref "R49") (pin "1") (pinfunction "1_1") (pintype "passive"))
      (node (ref "R50") (pin "2") (pinfunction "2_2") (pintype "passive"))
      (node (ref "RN1") (pin "1") (pinfunction "1_1") (pintype "passive"))
      (node (ref "RN3") (pin "1") (pinfunction "1_1") (pintype "passive"))
      (node (ref "SJ6") (pin "P$1") (pinfunction "1_P$1") (pintype "passive"))
      (node (ref "U3") (pin "16") (pinfunction "VCC_16") (pintype "power_in"))
      (node (ref "U3") (pin "9") (pinfunction "CLR_9") (pintype "input"))
      (node (ref "U4") (pin "1") (pinfunction "SER_1") (pintype "input"))
      (node (ref "U4") (pin "16") (pinfunction "VCC_16") (pintype "power_in"))
      (node (ref "U4") (pin "9") (pinfunction "CLR_9") (pintype "input"))
    )
    (net (code "2") (name "+5V") (class "Default")
      (node (ref "C1") (pin "1") (pinfunction "1_1") (pintype "passive"))
      (node (ref "C11") (pin "1") (pinfunction "1_1") (pintype "passive"))
      (node (ref "C2") (pin "1") (pinfunction "1_1") (pintype "passive"))
      (node (ref "C3") (pin "1") (pinfunction "1_1") (pintype "passive"))
      (node (ref "G1") (pin "5V2") (pinfunction "5V2_5V2") (pintype "power_in"))
      (node (ref "IC2") (pin "3") (pinfunction "VDD_3") (pintype "power_in"))
      (node (ref "JP1") (pin "3") (pinfunction "3_3") (pintype "passive"))
      (node (ref "JP1") (pin "4") (pinfunction "4_4") (pintype "passive"))
      (node (ref "JP10") (pin "6") (pinfunction "6_6") (pintype "passive"))
      (node (ref "JP2") (pin "3") (pinfunction "3_3") (pintype "passive"))
      (node (ref "JP2") (pin "4") (pinfunction "4_4") (pintype "passive"))
      (node (ref "JP3") (pin "3") (pinfunction "3_3") (pintype "passive"))
      (node (ref "JP3") (pin "4") (pinfunction "4_4") (pintype "passive"))
      (node (ref "JP4") (pin "3") (pinfunction "3_3") (pintype "passive"))
      (node (ref "JP4") (pin "4") (pinfunction "4_4") (pintype "passive"))
      (node (ref "JP5") (pin "6") (pinfunction "6_6") (pintype "passive"))
      (node (ref "JP6") (pin "3") (pinfunction "3_3") (pintype "passive"))
      (node (ref "JP8") (pin "6") (pinfunction "6_6") (pintype "passive"))
      (node (ref "JP9") (pin "6") (pinfunction "6_6") (pintype "passive"))
      (node (ref "R1") (pin "1") (pinfunction "1_1") (pintype "passive"))
      (node (ref "R10") (pin "1") (pinfunction "1_1") (pintype "passive"))
      (node (ref "R11") (pin "1") (pinfunction "1_1") (pintype "passive"))
      (node (ref "R12") (pin "1") (pinfunction "1_1") (pintype "passive"))
      (node (ref "R13") (pin "1") (pinfunction "1_1") (pintype "passive"))
      (node (ref "R14") (pin "1") (pinfunction "1_1") (pintype "passive"))
      (node (ref "R15") (pin "1") (pinfunction "1_1") (pintype "passive"))
      (node (ref "R2") (pin "1") (pinfunction "1_1") (pintype "passive"))
      (node (ref "R3") (pin "2") (pinfunction "2_2") (pintype "passive"))
      (node (ref "R4") (pin "2") (pinfunction "2_2") (pintype "passive"))
      (node (ref "R5") (pin "2") (pinfunction "2_2") (pintype "passive"))
      (node (ref "R6") (pin "1") (pinfunction "1_1") (pintype "passive"))
      (node (ref "R7") (pin "1") (pinfunction "1_1") (pintype "passive"))
      (node (ref "R8") (pin "1") (pinfunction "1_1") (pintype "passive"))
      (node (ref "R9") (pin "1") (pinfunction "1_1") (pintype "passive"))
      (node (ref "SJ15") (pin "P$2") (pinfunction "2_P$2") (pintype "passive"))
      (node (ref "SJ16") (pin "P$2") (pinfunction "2_P$2") (pintype "passive"))
      (node (ref "SJ8") (pin "P$2") (pinfunction "2_P$2") (pintype "passive"))
      (node (ref "SJ9") (pin "P$2") (pinfunction "2_P$2") (pintype "passive"))
      (node (ref "U1") (pin "3") (pinfunction "VCC_3") (pintype "power_in"))
      (node (ref "U11") (pin "10") (pinfunction "SCL_10") (pintype "input"))
      (node (ref "U11") (pin "16") (pinfunction "VCC_16") (pintype "power_in"))
      (node (ref "U13") (pin "10") (pinfunction "SCL_10") (pintype "input"))
      (node (ref "U13") (pin "16") (pinfunction "VCC_16") (pintype "power_in"))
      (node (ref "X6") (pin "1") (pinfunction "1_1") (pintype "passive"))
    )
    (net (code "3") (name "+12V") (class "Default")
      (node (ref "C10") (pin "1") (pinfunction "1_1") (pintype "passive"))
      (node (ref "C5") (pin "1") (pinfunction "1_1") (pintype "passive"))
      (node (ref "C9") (pin "1") (pinfunction "1_1") (pintype "passive"))
      (node (ref "D3") (pin "C") (pinfunction "C_C") (pintype "passive"))
      (node (ref "D4") (pin "C") (pinfunction "C_C") (pintype "passive"))
      (node (ref "IC1") (pin "5") (pinfunction "IN_5") (pintype "input"))
      (node (ref "JP5") (pin "7") (pinfunction "7_7") (pintype "passive"))
      (node (ref "JP7") (pin "2") (pinfunction "2_2") (pintype "passive"))
      (node (ref "SJ10") (pin "P$2") (pinfunction "2_P$2") (pintype "passive"))
      (node (ref "SJ11") (pin "P$2") (pinfunction "2_P$2") (pintype "passive"))
      (node (ref "SJ17") (pin "P$2") (pinfunction "2_P$2") (pintype "passive"))
      (node (ref "SJ18") (pin "P$2") (pinfunction "2_P$2") (pintype "passive"))
      (node (ref "SJ3") (pin "P$2") (pinfunction "2_P$2") (pintype "passive"))
      (node (ref "U10") (pin "6") (pinfunction "VDD_6") (pintype "power_in"))
      (node (ref "U2") (pin "1") (pinfunction "VIN_1") (pintype "bidirectional"))
      (node (ref "U5") (pin "6") (pinfunction "VDD_6") (pintype "power_in"))
      (node (ref "U6") (pin "4") (pinfunction "V+_4") (pintype "power_in"))
      (node (ref "U7") (pin "6") (pinfunction "VDD_6") (pintype "power_in"))
      (node (ref "U8") (pin "6") (pinfunction "VDD_6") (pintype "power_in"))
      (node (ref "U9") (pin "4") (pinfunction "V+_4") (pintype "power_in"))
    )
    (net (code "4") (name "/AGND") (class "Default")
      (node (ref "G1") (pin "AGND") (pinfunction "AGND_AGND") (pintype "power_in"))
    )
    (net (code "5") (name "/AVDD") (class "Default")
      (node (ref "G1") (pin "AVDD") (pinfunction "AVDD_AVDD") (pintype "power_in"))
    )
    (net (code "6") (name "/CANH") (class "Default")
      (node (ref "IC2") (pin "7") (pinfunction "CANH_7") (pintype "bidirectional"))
      (node (ref "U1") (pin "7") (pinfunction "CANH_7") (pintype "bidirectional"))
      (node (ref "X1") (pin "1") (pinfunction "1_1") (pintype "passive"))
      (node (ref "X2") (pin "1") (pinfunction "1_1") (pintype "passive"))
    )
    (net (code "7") (name "/CANL") (class "Default")
      (node (ref "IC2") (pin "6") (pinfunction "CANL_6") (pintype "bidirectional"))
      (node (ref "U1") (pin "6") (pinfunction "CANL_6") (pintype "bidirectional"))
      (node (ref "X1") (pin "2") (pinfunction "2_2") (pintype "passive"))
      (node (ref "X2") (pin "2") (pinfunction "2_2") (pintype "passive"))
    )
    (net (code "8") (name "/GND4") (class "Default")
      (node (ref "G1") (pin "GND4") (pinfunction "GND4_GND4") (pintype "power_in"))
    )
    (net (code "9") (name "/PWR_POS") (class "Default")
      (node (ref "R17") (pin "2") (pinfunction "2_2") (pintype "passive"))
      (node (ref "X1") (pin "8") (pinfunction "8_8") (pintype "passive"))
      (node (ref "X2") (pin "8") (pinfunction "8_8") (pintype "passive"))
    )
    (net (code "10") (name "/U5V") (class "Default")
      (node (ref "G1") (pin "U5V") (pinfunction "U5V_U5V") (pintype "power_in"))
    )
    (net (code "11") (name "/VBAT") (class "Default")
      (node (ref "G1") (pin "VBAT") (pinfunction "VBAT_VBAT") (pintype "power_in"))
    )
    (net (code "12") (name "/VDD") (class "Default")
      (node (ref "G1") (pin "VDD") (pinfunction "VDD_VDD") (pintype "power_in"))
    )
    (net (code "13") (name "CANRX") (class "Default")
      (node (ref "G1") (pin "PB8") (pinfunction "PB8_PB8") (pintype "bidirectional"))
      (node (ref "IC2") (pin "4") (pinfunction "RXD_4") (pintype "bidirectional"))
      (node (ref "U1") (pin "4") (pinfunction "RXD_4") (pintype "output"))
    )
    (net (code "14") (name "CANTX") (class "Default")
      (node (ref "G1") (pin "PB9") (pinfunction "PB9_PB9") (pintype "bidirectional"))
      (node (ref "IC2") (pin "1") (pinfunction "TXD_1") (pintype "bidirectional"))
      (node (ref "U1") (pin "1") (pinfunction "TXD_1") (pintype "input"))
    )
    (net (code "15") (name "E_CS") (class "Default")
      (node (ref "G1") (pin "PC10") (pinfunction "PC10_PC10") (pintype "bidirectional"))
      (node (ref "JP5") (pin "4") (pinfunction "4_4") (pintype "passive"))
      (node (ref "R1") (pin "2") (pinfunction "2_2") (pintype "passive"))
    )
    (net (code "16") (name "E_LAT") (class "Default")
      (node (ref "G1") (pin "PC11") (pinfunction "PC11_PC11") (pintype "bidirectional"))
      (node (ref "JP5") (pin "5") (pinfunction "5_5") (pintype "passive"))
      (node (ref "R2") (pin "2") (pinfunction "2_2") (pintype "passive"))
    )
    (net (code "17") (name "GND") (class "Default")
      (node (ref "C1") (pin "2") (pinfunction "2_2") (pintype "passive"))
      (node (ref "C10") (pin "2") (pinfunction "2_2") (pintype "passive"))
      (node (ref "C11") (pin "2") (pinfunction "2_2") (pintype "passive"))
      (node (ref "C2") (pin "2") (pinfunction "2_2") (pintype "passive"))
      (node (ref "C3") (pin "2") (pinfunction "2_2") (pintype "passive"))
      (node (ref "C4") (pin "2") (pinfunction "2_2") (pintype "passive"))
      (node (ref "C5") (pin "2") (pinfunction "2_2") (pintype "passive"))
      (node (ref "C6") (pin "-") (pinfunction "-_-") (pintype "passive"))
      (node (ref "C7") (pin "2") (pinfunction "2_2") (pintype "passive"))
      (node (ref "C8") (pin "2") (pinfunction "2_2") (pintype "passive"))
      (node (ref "C9") (pin "2") (pinfunction "2_2") (pintype "passive"))
      (node (ref "D5") (pin "A") (pinfunction "A_A") (pintype "passive"))
      (node (ref "D6") (pin "A") (pinfunction "A_A") (pintype "passive"))
      (node (ref "G1") (pin "GND3") (pinfunction "GND3_GND3") (pintype "power_in"))
      (node (ref "G1") (pin "GND5") (pinfunction "GND5_GND5") (pintype "power_in"))
      (node (ref "G1") (pin "GND6") (pinfunction "GND6_GND6") (pintype "power_in"))
      (node (ref "G1") (pin "GND7") (pinfunction "GND7_GND7") (pintype "power_in"))
      (node (ref "G1") (pin "GND8") (pinfunction "GND8_GND8") (pintype "power_in"))
      (node (ref "IC1") (pin "2") (pinfunction "GNDSIG_2") (pintype "input"))
      (node (ref "IC1") (pin "3") (pinfunction "~{ON/OFF}_3") (pintype "input"))
      (node (ref "IC1") (pin "4") (pinfunction "GND_4") (pintype "power_in"))
      (node (ref "IC2") (pin "2") (pinfunction "VSS_2") (pintype "power_in"))
      (node (ref "J1") (pin "2") (pinfunction "2_2") (pintype "passive"))
      (node (ref "J1") (pin "3") (pinfunction "3_3") (pintype "passive"))
      (node (ref "JP1") (pin "5") (pinfunction "5_5") (pintype "passive"))
      (node (ref "JP1") (pin "6") (pinfunction "6_6") (pintype "passive"))
      (node (ref "JP10") (pin "5") (pinfunction "5_5") (pintype "passive"))
      (node (ref "JP2") (pin "5") (pinfunction "5_5") (pintype "passive"))
      (node (ref "JP2") (pin "6") (pinfunction "6_6") (pintype "passive"))
      (node (ref "JP3") (pin "5") (pinfunction "5_5") (pintype "passive"))
      (node (ref "JP3") (pin "6") (pinfunction "6_6") (pintype "passive"))
      (node (ref "JP4") (pin "5") (pinfunction "5_5") (pintype "passive"))
      (node (ref "JP4") (pin "6") (pinfunction "6_6") (pintype "passive"))
      (node (ref "JP5") (pin "8") (pinfunction "8_8") (pintype "passive"))
      (node (ref "JP6") (pin "4") (pinfunction "4_4") (pintype "passive"))
      (node (ref "JP8") (pin "5") (pinfunction "5_5") (pintype "passive"))
      (node (ref "JP9") (pin "5") (pinfunction "5_5") (pintype "passive"))
      (node (ref "Q1") (pin "2") (pinfunction "S_2") (pintype "passive"))
      (node (ref "Q10") (pin "2") (pinfunction "S_2") (pintype "passive"))
      (node (ref "Q11") (pin "2") (pinfunction "S_2") (pintype "passive"))
      (node (ref "Q12") (pin "2") (pinfunction "S_2") (pintype "passive"))
      (node (ref "Q13") (pin "2") (pinfunction "S_2") (pintype "passive"))
      (node (ref "Q14") (pin "2") (pinfunction "S_2") (pintype "passive"))
      (node (ref "Q15") (pin "2") (pinfunction "S_2") (pintype "passive"))
      (node (ref "Q16") (pin "2") (pinfunction "S_2") (pintype "passive"))
      (node (ref "Q2") (pin "2") (pinfunction "S_2") (pintype "passive"))
      (node (ref "Q3") (pin "2") (pinfunction "S_2") (pintype "passive"))
      (node (ref "Q4") (pin "2") (pinfunction "S_2") (pintype "passive"))
      (node (ref "Q5") (pin "2") (pinfunction "S_2") (pintype "passive"))
      (node (ref "Q6") (pin "2") (pinfunction "S_2") (pintype "passive"))
      (node (ref "Q7") (pin "2") (pinfunction "S_2") (pintype "passive"))
      (node (ref "Q8") (pin "2") (pinfunction "S_2") (pintype "passive"))
      (node (ref "Q9") (pin "2") (pinfunction "S_2") (pintype "passive"))
      (node (ref "R16") (pin "2") (pinfunction "2_2") (pintype "passive"))
      (node (ref "R51") (pin "1") (pinfunction "1_1") (pintype "passive"))
      (node (ref "SJ12") (pin "2") (pinfunction "2_2") (pintype "passive"))
      (node (ref "SJ13") (pin "P$2") (pinfunction "2_P$2") (pintype "passive"))
      (node (ref "SJ19") (pin "2") (pinfunction "2_2") (pintype "passive"))
      (node (ref "SJ20") (pin "P$2") (pinfunction "2_P$2") (pintype "passive"))
      (node (ref "U1") (pin "2") (pinfunction "GND_2") (pintype "power_in"))
      (node (ref "U10") (pin "3") (pinfunction "VSS_3") (pintype "power_in"))
      (node (ref "U11") (pin "13") (pinfunction "G_13") (pintype "input"))
      (node (ref "U11") (pin "8") (pinfunction "GND_8") (pintype "power_in"))
      (node (ref "U13") (pin "13") (pinfunction "G_13") (pintype "input"))
      (node (ref "U13") (pin "8") (pinfunction "GND_8") (pintype "power_in"))
      (node (ref "U2") (pin "4") (pinfunction "SD_4") (pintype "bidirectional"))
      (node (ref "U2") (pin "5") (pinfunction "GND1_5") (pintype "power_in"))
      (node (ref "U2") (pin "6") (pinfunction "GND2_6") (pintype "power_in"))
      (node (ref "U2") (pin "7") (pinfunction "GND3_7") (pintype "power_in"))
      (node (ref "U2") (pin "8") (pinfunction "GND4_8") (pintype "power_in"))
      (node (ref "U3") (pin "6") (pinfunction "INH_6") (pintype "input"))
      (node (ref "U3") (pin "8") (pinfunction "GND_8") (pintype "power_in"))
      (node (ref "U4") (pin "6") (pinfunction "INH_6") (pintype "input"))
      (node (ref "U4") (pin "8") (pinfunction "GND_8") (pintype "power_in"))
      (node (ref "U5") (pin "3") (pinfunction "VSS_3") (pintype "power_in"))
      (node (ref "U6") (pin "11") (pinfunction "V-_11") (pintype "power_in"))
      (node (ref "U7") (pin "3") (pinfunction "VSS_3") (pintype "power_in"))
      (node (ref "U8") (pin "3") (pinfunction "VSS_3") (pintype "power_in"))
      (node (ref "U9") (pin "11") (pinfunction "V-_11") (pintype "power_in"))
      (node (ref "X1") (pin "3") (pinfunction "3_3") (pintype "passive"))
      (node (ref "X1") (pin "6") (pinfunction "6_6") (pintype "passive"))
      (node (ref "X1") (pin "7") (pinfunction "7_7") (pintype "passive"))
      (node (ref "X2") (pin "3") (pinfunction "3_3") (pintype "passive"))
      (node (ref "X2") (pin "6") (pinfunction "6_6") (pintype "passive"))
      (node (ref "X2") (pin "7") (pinfunction "7_7") (pintype "passive"))
      (node (ref "X3") (pin "2") (pinfunction "2_2") (pintype "passive"))
      (node (ref "X5") (pin "9") (pinfunction "9_9") (pintype "passive"))
      (node (ref "X6") (pin "2") (pinfunction "2_2") (pintype "passive"))
    )
    (net (code "18") (name "I2CSCL") (class "Default")
      (node (ref "G1") (pin "PB6") (pinfunction "PB6_PB6") (pintype "bidirectional"))
      (node (ref "JP6") (pin "1") (pinfunction "1_1") (pintype "passive"))
      (node (ref "R15") (pin "2") (pinfunction "2_2") (pintype "passive"))
    )
    (net (code "19") (name "I2CSDA") (class "Default")
      (node (ref "G1") (pin "PB7") (pinfunction "PB7_PB7") (pintype "bidirectional"))
      (node (ref "JP6") (pin "2") (pinfunction "2_2") (pintype "passive"))
      (node (ref "R14") (pin "2") (pinfunction "2_2") (pintype "passive"))
    )
    (net (code "20") (name "ILAT") (class "Default")
      (node (ref "G1") (pin "PA6") (pinfunction "PA6_PA6") (pintype "bidirectional"))
      (node (ref "U3") (pin "15") (pinfunction "SH/~{LD}_15") (pintype "input"))
      (node (ref "U4") (pin "15") (pinfunction "SH/~{LD}_15") (pintype "input"))
    )
    (net (code "21") (name "MISO") (class "Default")
      (node (ref "G1") (pin "PB4") (pinfunction "PB4_PB4") (pintype "bidirectional"))
      (node (ref "JP5") (pin "1") (pinfunction "1_1") (pintype "passive"))
    )
    (net (code "22") (name "MISO2") (class "Default")
      (node (ref "G1") (pin "PC2") (pinfunction "PC2_PC2") (pintype "bidirectional"))
      (node (ref "SJ1") (pin "P$2") (pinfunction "2_P$2") (pintype "passive"))
      (node (ref "SJ7") (pin "P$2") (pinfunction "2_P$2") (pintype "passive"))
      (node (ref "U3") (pin "13") (pinfunction "QH_13") (pintype "output"))
    )
    (net (code "23") (name "MOSI") (class "Default")
      (node (ref "G1") (pin "PB5") (pinfunction "PB5_PB5") (pintype "bidirectional"))
      (node (ref "R4") (pin "1") (pinfunction "1_1") (pintype "passive"))
      (node (ref "SJ14") (pin "P$2") (pinfunction "2_P$2") (pintype "passive"))
      (node (ref "SJ4") (pin "1") (pinfunction "1_1") (pintype "passive"))
      (node (ref "U13") (pin "14") (pinfunction "SER_14") (pintype "input"))
    )
    (net (code "24") (name "Net-(D1-PadA)") (class "Default")
      (node (ref "D1") (pin "A") (pinfunction "A_A") (pintype "passive"))
      (node (ref "D2") (pin "A") (pinfunction "A_A") (pintype "passive"))
      (node (ref "JP7") (pin "4") (pinfunction "4_4") (pintype "passive"))
    )
    (net (code "25") (name "Net-(D1-PadC)") (class "Default")
      (node (ref "D1") (pin "C") (pinfunction "C_C") (pintype "passive"))
      (node (ref "D2") (pin "C") (pinfunction "C_C") (pintype "passive"))
      (node (ref "JP7") (pin "1") (pinfunction "1_1") (pintype "passive"))
    )
    (net (code "26") (name "Net-(D3-PadA)") (class "Default")
      (node (ref "D3") (pin "A") (pinfunction "A_A") (pintype "passive"))
      (node (ref "D4") (pin "A") (pinfunction "A_A") (pintype "passive"))
      (node (ref "J1") (pin "1") (pinfunction "1_1") (pintype "passive"))
      (node (ref "X3") (pin "1") (pinfunction "1_1") (pintype "passive"))
    )
    (net (code "27") (name "Net-(IC1-OUT)") (class "Default")
      (node (ref "D5") (pin "C") (pinfunction "C_C") (pintype "passive"))
      (node (ref "D6") (pin "C") (pinfunction "C_C") (pintype "passive"))
      (node (ref "IC1") (pin "7") (pinfunction "OUT_7") (pintype "passive"))
      (node (ref "L1") (pin "2") (pinfunction "2_2") (pintype "passive"))
      (node (ref "U2") (pin "2") (pinfunction "VOUT_2") (pintype "bidirectional"))
    )
    (net (code "28") (name "Net-(IC2-RS)") (class "Default")
      (node (ref "IC2") (pin "8") (pinfunction "RS_8") (pintype "bidirectional"))
      (node (ref "R16") (pin "1") (pinfunction "1_1") (pintype "passive"))
      (node (ref "U1") (pin "8") (pinfunction "RS_8") (pintype "input"))
    )
    (net (code "29") (name "Net-(IC2-VREF)") (class "Default")
      (node (ref "IC2") (pin "5") (pinfunction "VREF_5") (pintype "bidirectional"))
      (node (ref "SJ6") (pin "P$2") (pinfunction "2_P$2") (pintype "passive"))
      (node (ref "U1") (pin "5") (pinfunction "VREF_5") (pintype "output"))
    )
    (net (code "30") (name "Net-(JP7-Pad3)") (class "Default")
      (node (ref "JP7") (pin "3") (pinfunction "3_3") (pintype "passive"))
      (node (ref "R17") (pin "1") (pinfunction "1_1") (pintype "passive"))
    )
    (net (code "31") (name "Net-(JP8-Pad10)") (class "Default")
      (node (ref "JP8") (pin "10") (pinfunction "10_10") (pintype "passive"))
      (node (ref "R25") (pin "2") (pinfunction "2_2") (pintype "passive"))
      (node (ref "R26") (pin "2") (pinfunction "2_2") (pintype "passive"))
      (node (ref "RN1") (pin "9") (pinfunction "9_9") (pintype "passive"))
      (node (ref "RN2") (pin "1") (pinfunction "1_1") (pintype "passive"))
      (node (ref "X4") (pin "1") (pinfunction "1_1") (pintype "passive"))
    )
    (net (code "32") (name "Net-(JP9-Pad10)") (class "Default")
      (node (ref "JP9") (pin "10") (pinfunction "10_10") (pintype "passive"))
      (node (ref "R41") (pin "2") (pinfunction "2_2") (pintype "passive"))
      (node (ref "R42") (pin "2") (pinfunction "2_2") (pintype "passive"))
      (node (ref "RN3") (pin "9") (pinfunction "9_9") (pintype "passive"))
      (node (ref "RN4") (pin "1") (pinfunction "1_1") (pintype "passive"))
      (node (ref "X5") (pin "1") (pinfunction "1_1") (pintype "passive"))
    )
    (net (code "33") (name "Net-(Q1-D)") (class "Default")
      (node (ref "Q1") (pin "3") (pinfunction "D_3") (pintype "passive"))
      (node (ref "U12") (pin "11") (pinfunction "O8_11") (pintype "open_collector"))
      (node (ref "X8") (pin "8") (pinfunction "8_8") (pintype "passive"))
    )
    (net (code "34") (name "Net-(Q1-G)") (class "Default")
      (node (ref "Q1") (pin "1") (pinfunction "G_1") (pintype "passive"))
      (node (ref "R52") (pin "2") (pinfunction "2_2") (pintype "passive"))
    )
    (net (code "35") (name "Net-(Q2-D)") (class "Default")
      (node (ref "Q2") (pin "3") (pinfunction "D_3") (pintype "passive"))
      (node (ref "U12") (pin "12") (pinfunction "O7_12") (pintype "open_collector"))
      (node (ref "X8") (pin "7") (pinfunction "7_7") (pintype "passive"))
    )
    (net (code "36") (name "Net-(Q2-G)") (class "Default")
      (node (ref "Q2") (pin "1") (pinfunction "G_1") (pintype "passive"))
      (node (ref "R53") (pin "2") (pinfunction "2_2") (pintype "passive"))
    )
    (net (code "37") (name "Net-(Q3-D)") (class "Default")
      (node (ref "Q3") (pin "3") (pinfunction "D_3") (pintype "passive"))
      (node (ref "U12") (pin "13") (pinfunction "O6_13") (pintype "open_collector"))
      (node (ref "X8") (pin "6") (pinfunction "6_6") (pintype "passive"))
    )
    (net (code "38") (name "Net-(Q3-G)") (class "Default")
      (node (ref "Q3") (pin "1") (pinfunction "G_1") (pintype "passive"))
      (node (ref "R54") (pin "2") (pinfunction "2_2") (pintype "passive"))
    )
    (net (code "39") (name "Net-(Q4-D)") (class "Default")
      (node (ref "Q4") (pin "3") (pinfunction "D_3") (pintype "passive"))
      (node (ref "U12") (pin "14") (pinfunction "O5_14") (pintype "open_collector"))
      (node (ref "X8") (pin "5") (pinfunction "5_5") (pintype "passive"))
    )
    (net (code "40") (name "Net-(Q4-G)") (class "Default")
      (node (ref "Q4") (pin "1") (pinfunction "G_1") (pintype "passive"))
      (node (ref "R55") (pin "2") (pinfunction "2_2") (pintype "passive"))
    )
    (net (code "41") (name "Net-(Q5-D)") (class "Default")
      (node (ref "Q5") (pin "3") (pinfunction "D_3") (pintype "passive"))
      (node (ref "U12") (pin "15") (pinfunction "O4_15") (pintype "open_collector"))
      (node (ref "X8") (pin "4") (pinfunction "4_4") (pintype "passive"))
    )
    (net (code "42") (name "Net-(Q5-G)") (class "Default")
      (node (ref "Q5") (pin "1") (pinfunction "G_1") (pintype "passive"))
      (node (ref "R56") (pin "2") (pinfunction "2_2") (pintype "passive"))
    )
    (net (code "43") (name "Net-(Q6-D)") (class "Default")
      (node (ref "Q6") (pin "3") (pinfunction "D_3") (pintype "passive"))
      (node (ref "U12") (pin "16") (pinfunction "O3_16") (pintype "open_collector"))
      (node (ref "X8") (pin "3") (pinfunction "3_3") (pintype "passive"))
    )
    (net (code "44") (name "Net-(Q6-G)") (class "Default")
      (node (ref "Q6") (pin "1") (pinfunction "G_1") (pintype "passive"))
      (node (ref "R57") (pin "2") (pinfunction "2_2") (pintype "passive"))
    )
    (net (code "45") (name "Net-(Q7-D)") (class "Default")
      (node (ref "Q7") (pin "3") (pinfunction "D_3") (pintype "passive"))
      (node (ref "U12") (pin "17") (pinfunction "O2_17") (pintype "open_collector"))
      (node (ref "X8") (pin "2") (pinfunction "2_2") (pintype "passive"))
    )
    (net (code "46") (name "Net-(Q7-G)") (class "Default")
      (node (ref "Q7") (pin "1") (pinfunction "G_1") (pintype "passive"))
      (node (ref "R58") (pin "2") (pinfunction "2_2") (pintype "passive"))
    )
    (net (code "47") (name "Net-(Q8-D)") (class "Default")
      (node (ref "Q8") (pin "3") (pinfunction "D_3") (pintype "passive"))
      (node (ref "U12") (pin "18") (pinfunction "O1_18") (pintype "open_collector"))
      (node (ref "X8") (pin "1") (pinfunction "1_1") (pintype "passive"))
    )
    (net (code "48") (name "Net-(Q8-G)") (class "Default")
      (node (ref "Q8") (pin "1") (pinfunction "G_1") (pintype "passive"))
      (node (ref "R59") (pin "2") (pinfunction "2_2") (pintype "passive"))
    )
    (net (code "49") (name "Net-(Q9-D)") (class "Default")
      (node (ref "Q9") (pin "3") (pinfunction "D_3") (pintype "passive"))
      (node (ref "U14") (pin "11") (pinfunction "O8_11") (pintype "open_collector"))
      (node (ref "X9") (pin "8") (pinfunction "8_8") (pintype "passive"))
    )
    (net (code "50") (name "Net-(Q9-G)") (class "Default")
      (node (ref "Q9") (pin "1") (pinfunction "G_1") (pintype "passive"))
      (node (ref "R60") (pin "2") (pinfunction "2_2") (pintype "passive"))
    )
    (net (code "51") (name "Net-(Q10-D)") (class "Default")
      (node (ref "Q10") (pin "3") (pinfunction "D_3") (pintype "passive"))
      (node (ref "U14") (pin "12") (pinfunction "O7_12") (pintype "open_collector"))
      (node (ref "X9") (pin "7") (pinfunction "7_7") (pintype "passive"))
    )
    (net (code "52") (name "Net-(Q10-G)") (class "Default")
      (node (ref "Q10") (pin "1") (pinfunction "G_1") (pintype "passive"))
      (node (ref "R61") (pin "2") (pinfunction "2_2") (pintype "passive"))
    )
    (net (code "53") (name "Net-(Q11-D)") (class "Default")
      (node (ref "Q11") (pin "3") (pinfunction "D_3") (pintype "passive"))
      (node (ref "U14") (pin "13") (pinfunction "O6_13") (pintype "open_collector"))
      (node (ref "X9") (pin "6") (pinfunction "6_6") (pintype "passive"))
    )
    (net (code "54") (name "Net-(Q11-G)") (class "Default")
      (node (ref "Q11") (pin "1") (pinfunction "G_1") (pintype "passive"))
      (node (ref "R62") (pin "2") (pinfunction "2_2") (pintype "passive"))
    )
    (net (code "55") (name "Net-(Q12-D)") (class "Default")
      (node (ref "Q12") (pin "3") (pinfunction "D_3") (pintype "passive"))
      (node (ref "U14") (pin "14") (pinfunction "O5_14") (pintype "open_collector"))
      (node (ref "X9") (pin "5") (pinfunction "5_5") (pintype "passive"))
    )
    (net (code "56") (name "Net-(Q12-G)") (class "Default")
      (node (ref "Q12") (pin "1") (pinfunction "G_1") (pintype "passive"))
      (node (ref "R63") (pin "2") (pinfunction "2_2") (pintype "passive"))
    )
    (net (code "57") (name "Net-(Q13-D)") (class "Default")
      (node (ref "Q13") (pin "3") (pinfunction "D_3") (pintype "passive"))
      (node (ref "U14") (pin "15") (pinfunction "O4_15") (pintype "open_collector"))
      (node (ref "X9") (pin "4") (pinfunction "4_4") (pintype "passive"))
    )
    (net (code "58") (name "Net-(Q13-G)") (class "Default")
      (node (ref "Q13") (pin "1") (pinfunction "G_1") (pintype "passive"))
      (node (ref "R64") (pin "2") (pinfunction "2_2") (pintype "passive"))
    )
    (net (code "59") (name "Net-(Q14-D)") (class "Default")
      (node (ref "Q14") (pin "3") (pinfunction "D_3") (pintype "passive"))
      (node (ref "U14") (pin "16") (pinfunction "O3_16") (pintype "open_collector"))
      (node (ref "X9") (pin "3") (pinfunction "3_3") (pintype "passive"))
    )
    (net (code "60") (name "Net-(Q14-G)") (class "Default")
      (node (ref "Q14") (pin "1") (pinfunction "G_1") (pintype "passive"))
      (node (ref "R65") (pin "2") (pinfunction "2_2") (pintype "passive"))
    )
    (net (code "61") (name "Net-(Q15-D)") (class "Default")
      (node (ref "Q15") (pin "3") (pinfunction "D_3") (pintype "passive"))
      (node (ref "U14") (pin "17") (pinfunction "O2_17") (pintype "open_collector"))
      (node (ref "X9") (pin "2") (pinfunction "2_2") (pintype "passive"))
    )
    (net (code "62") (name "Net-(Q15-G)") (class "Default")
      (node (ref "Q15") (pin "1") (pinfunction "G_1") (pintype "passive"))
      (node (ref "R66") (pin "2") (pinfunction "2_2") (pintype "passive"))
    )
    (net (code "63") (name "Net-(Q16-D)") (class "Default")
      (node (ref "Q16") (pin "3") (pinfunction "D_3") (pintype "passive"))
      (node (ref "U14") (pin "18") (pinfunction "O1_18") (pintype "open_collector"))
      (node (ref "X9") (pin "1") (pinfunction "1_1") (pintype "passive"))
    )
    (net (code "64") (name "Net-(Q16-G)") (class "Default")
      (node (ref "Q16") (pin "1") (pinfunction "G_1") (pintype "passive"))
      (node (ref "R67") (pin "2") (pinfunction "2_2") (pintype "passive"))
    )
    (net (code "65") (name "Net-(RN2A-2)") (class "Default")
      (node (ref "R25") (pin "1") (pinfunction "1_1") (pintype "passive"))
      (node (ref "RN2") (pin "16") (pinfunction "2_16") (pintype "passive"))
      (node (ref "U3") (pin "14") (pinfunction "H_14") (pintype "input"))
    )
    (net (code "66") (name "Net-(RN2B-1)") (class "Default")
      (node (ref "JP8") (pin "9") (pinfunction "9_9") (pintype "passive"))
      (node (ref "R24") (pin "2") (pinfunction "2_2") (pintype "passive"))
      (node (ref "R27") (pin "2") (pinfunction "2_2") (pintype "passive"))
      (node (ref "RN1") (pin "8") (pinfunction "8_8") (pintype "passive"))
      (node (ref "RN2") (pin "2") (pinfunction "1_2") (pintype "passive"))
      (node (ref "X4") (pin "2") (pinfunction "2_2") (pintype "passive"))
    )
    (net (code "67") (name "Net-(RN2B-2)") (class "Default")
      (node (ref "R24") (pin "1") (pinfunction "1_1") (pintype "passive"))
      (node (ref "RN2") (pin "15") (pinfunction "2_15") (pintype "passive"))
      (node (ref "U3") (pin "12") (pinfunction "G_12") (pintype "input"))
    )
    (net (code "68") (name "Net-(RN2C-1)") (class "Default")
      (node (ref "JP8") (pin "8") (pinfunction "8_8") (pintype "passive"))
      (node (ref "R23") (pin "2") (pinfunction "2_2") (pintype "passive"))
      (node (ref "R28") (pin "2") (pinfunction "2_2") (pintype "passive"))
      (node (ref "RN1") (pin "7") (pinfunction "7_7") (pintype "passive"))
      (node (ref "RN2") (pin "3") (pinfunction "1_3") (pintype "passive"))
      (node (ref "X4") (pin "3") (pinfunction "3_3") (pintype "passive"))
    )
    (net (code "69") (name "Net-(RN2C-2)") (class "Default")
      (node (ref "R23") (pin "1") (pinfunction "1_1") (pintype "passive"))
      (node (ref "RN2") (pin "14") (pinfunction "2_14") (pintype "passive"))
      (node (ref "U3") (pin "11") (pinfunction "F_11") (pintype "input"))
    )
    (net (code "70") (name "Net-(RN2D-1)") (class "Default")
      (node (ref "JP8") (pin "7") (pinfunction "7_7") (pintype "passive"))
      (node (ref "R22") (pin "2") (pinfunction "2_2") (pintype "passive"))
      (node (ref "R29") (pin "2") (pinfunction "2_2") (pintype "passive"))
      (node (ref "RN1") (pin "6") (pinfunction "6_6") (pintype "passive"))
      (node (ref "RN2") (pin "4") (pinfunction "1_4") (pintype "passive"))
      (node (ref "X4") (pin "4") (pinfunction "4_4") (pintype "passive"))
    )
    (net (code "71") (name "Net-(RN2D-2)") (class "Default")
      (node (ref "R22") (pin "1") (pinfunction "1_1") (pintype "passive"))
      (node (ref "RN2") (pin "13") (pinfunction "2_13") (pintype "passive"))
      (node (ref "U3") (pin "10") (pinfunction "E_10") (pintype "input"))
    )
    (net (code "72") (name "Net-(RN2E-1)") (class "Default")
      (node (ref "JP8") (pin "4") (pinfunction "4_4") (pintype "passive"))
      (node (ref "R21") (pin "2") (pinfunction "2_2") (pintype "passive"))
      (node (ref "R30") (pin "2") (pinfunction "2_2") (pintype "passive"))
      (node (ref "RN1") (pin "5") (pinfunction "5_5") (pintype "passive"))
      (node (ref "RN2") (pin "5") (pinfunction "1_5") (pintype "passive"))
      (node (ref "X4") (pin "5") (pinfunction "5_5") (pintype "passive"))
    )
    (net (code "73") (name "Net-(RN2E-2)") (class "Default")
      (node (ref "R21") (pin "1") (pinfunction "1_1") (pintype "passive"))
      (node (ref "RN2") (pin "12") (pinfunction "2_12") (pintype "passive"))
      (node (ref "U3") (pin "5") (pinfunction "D_5") (pintype "input"))
    )
    (net (code "74") (name "Net-(RN2F-1)") (class "Default")
      (node (ref "JP8") (pin "3") (pinfunction "3_3") (pintype "passive"))
      (node (ref "R20") (pin "2") (pinfunction "2_2") (pintype "passive"))
      (node (ref "R31") (pin "2") (pinfunction "2_2") (pintype "passive"))
      (node (ref "RN1") (pin "4") (pinfunction "4_4") (pintype "passive"))
      (node (ref "RN2") (pin "6") (pinfunction "1_6") (pintype "passive"))
      (node (ref "X4") (pin "6") (pinfunction "6_6") (pintype "passive"))
    )
    (net (code "75") (name "Net-(RN2F-2)") (class "Default")
      (node (ref "R20") (pin "1") (pinfunction "1_1") (pintype "passive"))
      (node (ref "RN2") (pin "11") (pinfunction "2_11") (pintype "passive"))
      (node (ref "U3") (pin "4") (pinfunction "C_4") (pintype "input"))
    )
    (net (code "76") (name "Net-(RN2G-1)") (class "Default")
      (node (ref "JP8") (pin "2") (pinfunction "2_2") (pintype "passive"))
      (node (ref "R19") (pin "2") (pinfunction "2_2") (pintype "passive"))
      (node (ref "R32") (pin "2") (pinfunction "2_2") (pintype "passive"))
      (node (ref "RN1") (pin "3") (pinfunction "3_3") (pintype "passive"))
      (node (ref "RN2") (pin "7") (pinfunction "1_7") (pintype "passive"))
      (node (ref "X4") (pin "7") (pinfunction "7_7") (pintype "passive"))
    )
    (net (code "77") (name "Net-(RN2G-2)") (class "Default")
      (node (ref "R19") (pin "1") (pinfunction "1_1") (pintype "passive"))
      (node (ref "RN2") (pin "10") (pinfunction "2_10") (pintype "passive"))
      (node (ref "U3") (pin "3") (pinfunction "B_3") (pintype "input"))
    )
    (net (code "78") (name "Net-(RN2H-1)") (class "Default")
      (node (ref "JP8") (pin "1") (pinfunction "1_1") (pintype "passive"))
      (node (ref "R18") (pin "2") (pinfunction "2_2") (pintype "passive"))
      (node (ref "R33") (pin "2") (pinfunction "2_2") (pintype "passive"))
      (node (ref "RN1") (pin "2") (pinfunction "2_2") (pintype "passive"))
      (node (ref "RN2") (pin "8") (pinfunction "1_8") (pintype "passive"))
      (node (ref "X4") (pin "8") (pinfunction "8_8") (pintype "passive"))
    )
    (net (code "79") (name "Net-(RN2H-2)") (class "Default")
      (node (ref "R18") (pin "1") (pinfunction "1_1") (pintype "passive"))
      (node (ref "RN2") (pin "9") (pinfunction "2_9") (pintype "passive"))
      (node (ref "U3") (pin "2") (pinfunction "A_2") (pintype "input"))
    )
    (net (code "80") (name "Net-(RN4A-2)") (class "Default")
      (node (ref "R41") (pin "1") (pinfunction "1_1") (pintype "passive"))
      (node (ref "RN4") (pin "16") (pinfunction "2_16") (pintype "passive"))
      (node (ref "U4") (pin "14") (pinfunction "H_14") (pintype "input"))
    )
    (net (code "81") (name "Net-(RN4B-1)") (class "Default")
      (node (ref "JP9") (pin "9") (pinfunction "9_9") (pintype "passive"))
      (node (ref "R40") (pin "2") (pinfunction "2_2") (pintype "passive"))
      (node (ref "R43") (pin "2") (pinfunction "2_2") (pintype "passive"))
      (node (ref "RN3") (pin "8") (pinfunction "8_8") (pintype "passive"))
      (node (ref "RN4") (pin "2") (pinfunction "1_2") (pintype "passive"))
      (node (ref "X5") (pin "2") (pinfunction "2_2") (pintype "passive"))
    )
    (net (code "82") (name "Net-(RN4B-2)") (class "Default")
      (node (ref "R40") (pin "1") (pinfunction "1_1") (pintype "passive"))
      (node (ref "RN4") (pin "15") (pinfunction "2_15") (pintype "passive"))
      (node (ref "U4") (pin "12") (pinfunction "G_12") (pintype "input"))
    )
    (net (code "83") (name "Net-(RN4C-1)") (class "Default")
      (node (ref "JP9") (pin "8") (pinfunction "8_8") (pintype "passive"))
      (node (ref "R39") (pin "2") (pinfunction "2_2") (pintype "passive"))
      (node (ref "R44") (pin "2") (pinfunction "2_2") (pintype "passive"))
      (node (ref "RN3") (pin "7") (pinfunction "7_7") (pintype "passive"))
      (node (ref "RN4") (pin "3") (pinfunction "1_3") (pintype "passive"))
      (node (ref "X5") (pin "3") (pinfunction "3_3") (pintype "passive"))
    )
    (net (code "84") (name "Net-(RN4C-2)") (class "Default")
      (node (ref "R39") (pin "1") (pinfunction "1_1") (pintype "passive"))
      (node (ref "RN4") (pin "14") (pinfunction "2_14") (pintype "passive"))
      (node (ref "U4") (pin "11") (pinfunction "F_11") (pintype "input"))
    )
    (net (code "85") (name "Net-(RN4D-1)") (class "Default")
      (node (ref "JP9") (pin "7") (pinfunction "7_7") (pintype "passive"))
      (node (ref "R38") (pin "2") (pinfunction "2_2") (pintype "passive"))
      (node (ref "R45") (pin "2") (pinfunction "2_2") (pintype "passive"))
      (node (ref "RN3") (pin "6") (pinfunction "6_6") (pintype "passive"))
      (node (ref "RN4") (pin "4") (pinfunction "1_4") (pintype "passive"))
      (node (ref "X5") (pin "4") (pinfunction "4_4") (pintype "passive"))
    )
    (net (code "86") (name "Net-(RN4D-2)") (class "Default")
      (node (ref "R38") (pin "1") (pinfunction "1_1") (pintype "passive"))
      (node (ref "RN4") (pin "13") (pinfunction "2_13") (pintype "passive"))
      (node (ref "U4") (pin "10") (pinfunction "E_10") (pintype "input"))
    )
    (net (code "87") (name "Net-(RN4E-1)") (class "Default")
      (node (ref "JP9") (pin "4") (pinfunction "4_4") (pintype "passive"))
      (node (ref "R37") (pin "2") (pinfunction "2_2") (pintype "passive"))
      (node (ref "R46") (pin "2") (pinfunction "2_2") (pintype "passive"))
      (node (ref "RN3") (pin "5") (pinfunction "5_5") (pintype "passive"))
      (node (ref "RN4") (pin "5") (pinfunction "1_5") (pintype "passive"))
      (node (ref "X5") (pin "5") (pinfunction "5_5") (pintype "passive"))
    )
    (net (code "88") (name "Net-(RN4E-2)") (class "Default")
      (node (ref "R37") (pin "1") (pinfunction "1_1") (pintype "passive"))
      (node (ref "RN4") (pin "12") (pinfunction "2_12") (pintype "passive"))
      (node (ref "U4") (pin "5") (pinfunction "D_5") (pintype "input"))
    )
    (net (code "89") (name "Net-(RN4F-1)") (class "Default")
      (node (ref "JP9") (pin "3") (pinfunction "3_3") (pintype "passive"))
      (node (ref "R36") (pin "2") (pinfunction "2_2") (pintype "passive"))
      (node (ref "R47") (pin "2") (pinfunction "2_2") (pintype "passive"))
      (node (ref "RN3") (pin "4") (pinfunction "4_4") (pintype "passive"))
      (node (ref "RN4") (pin "6") (pinfunction "1_6") (pintype "passive"))
      (node (ref "X5") (pin "6") (pinfunction "6_6") (pintype "passive"))
    )
    (net (code "90") (name "Net-(RN4F-2)") (class "Default")
      (node (ref "R36") (pin "1") (pinfunction "1_1") (pintype "passive"))
      (node (ref "RN4") (pin "11") (pinfunction "2_11") (pintype "passive"))
      (node (ref "U4") (pin "4") (pinfunction "C_4") (pintype "input"))
    )
    (net (code "91") (name "Net-(RN4G-1)") (class "Default")
      (node (ref "JP9") (pin "2") (pinfunction "2_2") (pintype "passive"))
      (node (ref "R35") (pin "2") (pinfunction "2_2") (pintype "passive"))
      (node (ref "R48") (pin "2") (pinfunction "2_2") (pintype "passive"))
      (node (ref "RN3") (pin "3") (pinfunction "3_3") (pintype "passive"))
      (node (ref "RN4") (pin "7") (pinfunction "1_7") (pintype "passive"))
      (node (ref "X5") (pin "7") (pinfunction "7_7") (pintype "passive"))
    )
    (net (code "92") (name "Net-(RN4G-2)") (class "Default")
      (node (ref "R35") (pin "1") (pinfunction "1_1") (pintype "passive"))
      (node (ref "RN4") (pin "10") (pinfunction "2_10") (pintype "passive"))
      (node (ref "U4") (pin "3") (pinfunction "B_3") (pintype "input"))
    )
    (net (code "93") (name "Net-(RN4H-1)") (class "Default")
      (node (ref "JP9") (pin "1") (pinfunction "1_1") (pintype "passive"))
      (node (ref "R34") (pin "2") (pinfunction "2_2") (pintype "passive"))
      (node (ref "R49") (pin "2") (pinfunction "2_2") (pintype "passive"))
      (node (ref "RN3") (pin "2") (pinfunction "2_2") (pintype "passive"))
      (node (ref "RN4") (pin "8") (pinfunction "1_8") (pintype "passive"))
      (node (ref "X5") (pin "8") (pinfunction "8_8") (pintype "passive"))
    )
    (net (code "94") (name "Net-(RN4H-2)") (class "Default")
      (node (ref "R34") (pin "1") (pinfunction "1_1") (pintype "passive"))
      (node (ref "RN4") (pin "9") (pinfunction "2_9") (pintype "passive"))
      (node (ref "U4") (pin "2") (pinfunction "A_2") (pintype "input"))
    )
    (net (code "95") (name "Net-(SJ1-1)") (class "Default")
      (node (ref "G1") (pin "PB14") (pinfunction "PB14_PB14") (pintype "bidirectional"))
      (node (ref "SJ1") (pin "P$1") (pinfunction "1_P$1") (pintype "passive"))
    )
    (net (code "96") (name "Net-(SJ2-2)") (class "Default")
      (node (ref "G1") (pin "PB13") (pinfunction "PB13_PB13") (pintype "bidirectional"))
      (node (ref "SJ2") (pin "P$2") (pinfunction "2_P$2") (pintype "passive"))
    )
    (net (code "97") (name "Net-(SJ3-1)") (class "Default")
      (node (ref "G1") (pin "VIN2") (pinfunction "VIN2_VIN2") (pintype "power_in"))
      (node (ref "SJ3") (pin "P$1") (pinfunction "1_P$1") (pintype "passive"))
    )
    (net (code "98") (name "Net-(SJ5-2)") (class "Default")
      (node (ref "JP5") (pin "2") (pinfunction "2_2") (pintype "passive"))
      (node (ref "SJ4") (pin "2") (pinfunction "2_2") (pintype "passive"))
      (node (ref "SJ5") (pin "P$2") (pinfunction "2_P$2") (pintype "passive"))
    )
    (net (code "99") (name "Net-(SJ10-1)") (class "Default")
      (node (ref "SJ10") (pin "P$1") (pinfunction "1_P$1") (pintype "passive"))
      (node (ref "SJ12") (pin "1") (pinfunction "1_1") (pintype "passive"))
      (node (ref "SJ8") (pin "P$1") (pinfunction "1_P$1") (pintype "passive"))
      (node (ref "U12") (pin "9") (pinfunction "GND_9") (pintype "power_in"))
    )
    (net (code "100") (name "Net-(SJ11-1)") (class "Default")
      (node (ref "SJ11") (pin "P$1") (pinfunction "1_P$1") (pintype "passive"))
      (node (ref "SJ13") (pin "P$1") (pinfunction "1_P$1") (pintype "passive"))
      (node (ref "SJ9") (pin "P$1") (pinfunction "1_P$1") (pintype "passive"))
      (node (ref "U12") (pin "10") (pinfunction "CD+_10") (pintype "passive"))
      (node (ref "X8") (pin "9") (pinfunction "9_9") (pintype "passive"))
    )
    (net (code "101") (name "Net-(SJ15-1)") (class "Default")
      (node (ref "SJ15") (pin "P$1") (pinfunction "1_P$1") (pintype "passive"))
      (node (ref "SJ17") (pin "P$1") (pinfunction "1_P$1") (pintype "passive"))
      (node (ref "SJ19") (pin "1") (pinfunction "1_1") (pintype "passive"))
      (node (ref "U14") (pin "9") (pinfunction "GND_9") (pintype "power_in"))
    )
    (net (code "102") (name "Net-(SJ16-1)") (class "Default")
      (node (ref "SJ16") (pin "P$1") (pinfunction "1_P$1") (pintype "passive"))
      (node (ref "SJ18") (pin "P$1") (pinfunction "1_P$1") (pintype "passive"))
      (node (ref "SJ20") (pin "P$1") (pinfunction "1_P$1") (pintype "passive"))
      (node (ref "U14") (pin "10") (pinfunction "CD+_10") (pintype "passive"))
      (node (ref "X9") (pin "9") (pinfunction "9_9") (pintype "passive"))
    )
    (net (code "103") (name "Net-(U5A-O)") (class "Default")
      (node (ref "JP10") (pin "10") (pinfunction "10_10") (pintype "passive"))
      (node (ref "U5") (pin "7") (pinfunction "O_7") (pintype "output"))
      (node (ref "U6") (pin "7") (pinfunction "OUT_7") (pintype "output"))
      (node (ref "X7") (pin "1") (pinfunction "1_1") (pintype "passive"))
    )
    (net (code "104") (name "Net-(U5B-O)") (class "Default")
      (node (ref "JP10") (pin "9") (pinfunction "9_9") (pintype "passive"))
      (node (ref "U5") (pin "5") (pinfunction "O_5") (pintype "output"))
      (node (ref "U6") (pin "8") (pinfunction "OUT_8") (pintype "output"))
      (node (ref "X7") (pin "2") (pinfunction "2_2") (pintype "passive"))
    )
    (net (code "105") (name "Net-(U6A--IN)") (class "Default")
      (node (ref "R50") (pin "1") (pinfunction "1_1") (pintype "passive"))
      (node (ref "R51") (pin "2") (pinfunction "2_2") (pintype "passive"))
      (node (ref "U6") (pin "13") (pinfunction "-IN_13") (pintype "input"))
      (node (ref "U6") (pin "2") (pinfunction "-IN_2") (pintype "input"))
      (node (ref "U6") (pin "6") (pinfunction "-IN_6") (pintype "input"))
      (node (ref "U6") (pin "9") (pinfunction "-IN_9") (pintype "input"))
      (node (ref "U9") (pin "13") (pinfunction "-IN_13") (pintype "input"))
      (node (ref "U9") (pin "2") (pinfunction "-IN_2") (pintype "input"))
      (node (ref "U9") (pin "6") (pinfunction "-IN_6") (pintype "input"))
      (node (ref "U9") (pin "9") (pinfunction "-IN_9") (pintype "input"))
    )
    (net (code "106") (name "Net-(U6A-OUT)") (class "Default")
      (node (ref "JP10") (pin "8") (pinfunction "8_8") (pintype "passive"))
      (node (ref "U6") (pin "1") (pinfunction "OUT_1") (pintype "output"))
      (node (ref "U7") (pin "5") (pinfunction "O_5") (pintype "output"))
      (node (ref "X7") (pin "3") (pinfunction "3_3") (pintype "passive"))
    )
    (net (code "107") (name "Net-(U6D-OUT)") (class "Default")
      (node (ref "JP10") (pin "7") (pinfunction "7_7") (pintype "passive"))
      (node (ref "U6") (pin "14") (pinfunction "OUT_14") (pintype "output"))
      (node (ref "U7") (pin "7") (pinfunction "O_7") (pintype "output"))
      (node (ref "X7") (pin "4") (pinfunction "4_4") (pintype "passive"))
    )
    (net (code "108") (name "Net-(U8A-O)") (class "Default")
      (node (ref "JP10") (pin "4") (pinfunction "4_4") (pintype "passive"))
      (node (ref "U8") (pin "7") (pinfunction "O_7") (pintype "output"))
      (node (ref "U9") (pin "7") (pinfunction "OUT_7") (pintype "output"))
      (node (ref "X7") (pin "5") (pinfunction "5_5") (pintype "passive"))
    )
    (net (code "109") (name "Net-(U8B-O)") (class "Default")
      (node (ref "JP10") (pin "3") (pinfunction "3_3") (pintype "passive"))
      (node (ref "U8") (pin "5") (pinfunction "O_5") (pintype "output"))
      (node (ref "U9") (pin "8") (pinfunction "OUT_8") (pintype "output"))
      (node (ref "X7") (pin "6") (pinfunction "6_6") (pintype "passive"))
    )
    (net (code "110") (name "Net-(U10A-O)") (class "Default")
      (node (ref "JP10") (pin "1") (pinfunction "1_1") (pintype "passive"))
      (node (ref "U10") (pin "7") (pinfunction "O_7") (pintype "output"))
      (node (ref "U9") (pin "14") (pinfunction "OUT_14") (pintype "output"))
      (node (ref "X7") (pin "8") (pinfunction "8_8") (pintype "passive"))
    )
    (net (code "111") (name "Net-(U10B-O)") (class "Default")
      (node (ref "JP10") (pin "2") (pinfunction "2_2") (pintype "passive"))
      (node (ref "U10") (pin "5") (pinfunction "O_5") (pintype "output"))
      (node (ref "U9") (pin "1") (pinfunction "OUT_1") (pintype "output"))
      (node (ref "X7") (pin "7") (pinfunction "7_7") (pintype "passive"))
    )
    (net (code "112") (name "Net-(U11A-QA)") (class "Default")
      (node (ref "R59") (pin "1") (pinfunction "1_1") (pintype "passive"))
      (node (ref "U11") (pin "15") (pinfunction "QA_15") (pintype "tri_state"))
      (node (ref "U12") (pin "1") (pinfunction "I1_1") (pintype "input"))
    )
    (net (code "113") (name "Net-(U11A-QB)") (class "Default")
      (node (ref "R58") (pin "1") (pinfunction "1_1") (pintype "passive"))
      (node (ref "U11") (pin "1") (pinfunction "QB_1") (pintype "tri_state"))
      (node (ref "U12") (pin "2") (pinfunction "I2_2") (pintype "input"))
    )
    (net (code "114") (name "Net-(U11A-QC)") (class "Default")
      (node (ref "R57") (pin "1") (pinfunction "1_1") (pintype "passive"))
      (node (ref "U11") (pin "2") (pinfunction "QC_2") (pintype "tri_state"))
      (node (ref "U12") (pin "3") (pinfunction "I3_3") (pintype "input"))
    )
    (net (code "115") (name "Net-(U11A-QD)") (class "Default")
      (node (ref "R56") (pin "1") (pinfunction "1_1") (pintype "passive"))
      (node (ref "U11") (pin "3") (pinfunction "QD_3") (pintype "tri_state"))
      (node (ref "U12") (pin "4") (pinfunction "I4_4") (pintype "input"))
    )
    (net (code "116") (name "Net-(U11A-QE)") (class "Default")
      (node (ref "R55") (pin "1") (pinfunction "1_1") (pintype "passive"))
      (node (ref "U11") (pin "4") (pinfunction "QE_4") (pintype "tri_state"))
      (node (ref "U12") (pin "5") (pinfunction "I5_5") (pintype "input"))
    )
    (net (code "117") (name "Net-(U11A-QF)") (class "Default")
      (node (ref "R54") (pin "1") (pinfunction "1_1") (pintype "passive"))
      (node (ref "U11") (pin "5") (pinfunction "QF_5") (pintype "tri_state"))
      (node (ref "U12") (pin "6") (pinfunction "I6_6") (pintype "input"))
    )
    (net (code "118") (name "Net-(U11A-QG)") (class "Default")
      (node (ref "R53") (pin "1") (pinfunction "1_1") (pintype "passive"))
      (node (ref "U11") (pin "6") (pinfunction "QG_6") (pintype "tri_state"))
      (node (ref "U12") (pin "7") (pinfunction "I7_7") (pintype "input"))
    )
    (net (code "119") (name "Net-(U11A-QH)") (class "Default")
      (node (ref "R52") (pin "1") (pinfunction "1_1") (pintype "passive"))
      (node (ref "U11") (pin "7") (pinfunction "QH_7") (pintype "tri_state"))
      (node (ref "U12") (pin "8") (pinfunction "I8_8") (pintype "input"))
    )
    (net (code "120") (name "Net-(U13A-QA)") (class "Default")
      (node (ref "R67") (pin "1") (pinfunction "1_1") (pintype "passive"))
      (node (ref "U13") (pin "15") (pinfunction "QA_15") (pintype "tri_state"))
      (node (ref "U14") (pin "1") (pinfunction "I1_1") (pintype "input"))
    )
    (net (code "121") (name "Net-(U13A-QB)") (class "Default")
      (node (ref "R66") (pin "1") (pinfunction "1_1") (pintype "passive"))
      (node (ref "U13") (pin "1") (pinfunction "QB_1") (pintype "tri_state"))
      (node (ref "U14") (pin "2") (pinfunction "I2_2") (pintype "input"))
    )
    (net (code "122") (name "Net-(U13A-QC)") (class "Default")
      (node (ref "R65") (pin "1") (pinfunction "1_1") (pintype "passive"))
      (node (ref "U13") (pin "2") (pinfunction "QC_2") (pintype "tri_state"))
      (node (ref "U14") (pin "3") (pinfunction "I3_3") (pintype "input"))
    )
    (net (code "123") (name "Net-(U13A-QD)") (class "Default")
      (node (ref "R64") (pin "1") (pinfunction "1_1") (pintype "passive"))
      (node (ref "U13") (pin "3") (pinfunction "QD_3") (pintype "tri_state"))
      (node (ref "U14") (pin "4") (pinfunction "I4_4") (pintype "input"))
    )
    (net (code "124") (name "Net-(U13A-QE)") (class "Default")
      (node (ref "R63") (pin "1") (pinfunction "1_1") (pintype "passive"))
      (node (ref "U13") (pin "4") (pinfunction "QE_4") (pintype "tri_state"))
      (node (ref "U14") (pin "5") (pinfunction "I5_5") (pintype "input"))
    )
    (net (code "125") (name "Net-(U13A-QF)") (class "Default")
      (node (ref "R62") (pin "1") (pinfunction "1_1") (pintype "passive"))
      (node (ref "U13") (pin "5") (pinfunction "QF_5") (pintype "tri_state"))
      (node (ref "U14") (pin "6") (pinfunction "I6_6") (pintype "input"))
    )
    (net (code "126") (name "Net-(U13A-QG)") (class "Default")
      (node (ref "R61") (pin "1") (pinfunction "1_1") (pintype "passive"))
      (node (ref "U13") (pin "6") (pinfunction "QG_6") (pintype "tri_state"))
      (node (ref "U14") (pin "7") (pinfunction "I7_7") (pintype "input"))
    )
    (net (code "127") (name "Net-(U13A-QH)") (class "Default")
      (node (ref "R60") (pin "1") (pinfunction "1_1") (pintype "passive"))
      (node (ref "U13") (pin "7") (pinfunction "QH_7") (pintype "tri_state"))
      (node (ref "U14") (pin "8") (pinfunction "I8_8") (pintype "input"))
    )
    (net (code "128") (name "Net-(X1-Pad4)") (class "Default")
      (node (ref "X1") (pin "4") (pinfunction "4_4") (pintype "passive"))
      (node (ref "X2") (pin "4") (pinfunction "4_4") (pintype "passive"))
    )
    (net (code "129") (name "Net-(X1-Pad5)") (class "Default")
      (node (ref "X1") (pin "5") (pinfunction "5_5") (pintype "passive"))
      (node (ref "X2") (pin "5") (pinfunction "5_5") (pintype "passive"))
    )
    (net (code "130") (name "OLAT") (class "Default")
      (node (ref "G1") (pin "PA8") (pinfunction "PA8_PA8") (pintype "bidirectional"))
      (node (ref "R3") (pin "1") (pinfunction "1_1") (pintype "passive"))
      (node (ref "U11") (pin "12") (pinfunction "RCK_12") (pintype "input"))
      (node (ref "U13") (pin "12") (pinfunction "RCK_12") (pintype "input"))
    )
    (net (code "131") (name "SCK") (class "Default")
      (node (ref "G1") (pin "PB3") (pinfunction "PB3_PB3") (pintype "bidirectional"))
      (node (ref "JP5") (pin "3") (pinfunction "3_3") (pintype "passive"))
      (node (ref "R5") (pin "1") (pinfunction "1_1") (pintype "passive"))
      (node (ref "U11") (pin "11") (pinfunction "SCK_11") (pintype "input"))
      (node (ref "U13") (pin "11") (pinfunction "SCK_11") (pintype "input"))
    )
    (net (code "132") (name "SCK2") (class "Default")
      (node (ref "G1") (pin "PB10") (pinfunction "PB10_PB10") (pintype "bidirectional"))
      (node (ref "SJ2") (pin "P$1") (pinfunction "1_P$1") (pintype "passive"))
      (node (ref "U3") (pin "7") (pinfunction "CLK_7") (pintype "input"))
      (node (ref "U4") (pin "7") (pinfunction "CLK_7") (pintype "input"))
    )
    (net (code "133") (name "SLNK1") (class "Default")
      (node (ref "SJ14") (pin "P$1") (pinfunction "1_P$1") (pintype "passive"))
      (node (ref "U11") (pin "14") (pinfunction "SER_14") (pintype "input"))
      (node (ref "U13") (pin "9") (pinfunction "QH*_9") (pintype "tri_state"))
    )
    (net (code "134") (name "SLNK2") (class "Default")
      (node (ref "SJ5") (pin "P$1") (pinfunction "1_P$1") (pintype "passive"))
      (node (ref "U11") (pin "9") (pinfunction "QH*_9") (pintype "tri_state"))
    )
    (net (code "135") (name "SLNK3") (class "Default")
      (node (ref "SJ7") (pin "P$1") (pinfunction "1_P$1") (pintype "passive"))
      (node (ref "U3") (pin "1") (pinfunction "SER_1") (pintype "input"))
      (node (ref "U4") (pin "13") (pinfunction "QH_13") (pintype "output"))
    )
    (net (code "136") (name "SRV1") (class "Default")
      (node (ref "G1") (pin "PC9") (pinfunction "PC9_PC9") (pintype "bidirectional"))
      (node (ref "JP4") (pin "2") (pinfunction "2_2") (pintype "passive"))
      (node (ref "R13") (pin "2") (pinfunction "2_2") (pintype "passive"))
    )
    (net (code "137") (name "SRV2") (class "Default")
      (node (ref "G1") (pin "PC7") (pinfunction "PC7_PC7") (pintype "bidirectional"))
      (node (ref "JP4") (pin "1") (pinfunction "1_1") (pintype "passive"))
      (node (ref "R12") (pin "2") (pinfunction "2_2") (pintype "passive"))
    )
    (net (code "138") (name "SRV3") (class "Default")
      (node (ref "G1") (pin "PC8") (pinfunction "PC8_PC8") (pintype "bidirectional"))
      (node (ref "JP3") (pin "2") (pinfunction "2_2") (pintype "passive"))
      (node (ref "R11") (pin "2") (pinfunction "2_2") (pintype "passive"))
    )
    (net (code "139") (name "SRV4") (class "Default")
      (node (ref "G1") (pin "PC6") (pinfunction "PC6_PC6") (pintype "bidirectional"))
      (node (ref "JP3") (pin "1") (pinfunction "1_1") (pintype "passive"))
      (node (ref "R10") (pin "2") (pinfunction "2_2") (pintype "passive"))
    )
    (net (code "140") (name "SRV5") (class "Default")
      (node (ref "G1") (pin "PC12") (pinfunction "PC12_PC12") (pintype "bidirectional"))
      (node (ref "JP2") (pin "2") (pinfunction "2_2") (pintype "passive"))
      (node (ref "R9") (pin "2") (pinfunction "2_2") (pintype "passive"))
    )
    (net (code "141") (name "SRV6") (class "Default")
      (node (ref "G1") (pin "PA15") (pinfunction "PA15_PA15") (pintype "bidirectional"))
      (node (ref "JP2") (pin "1") (pinfunction "1_1") (pintype "passive"))
      (node (ref "R8") (pin "2") (pinfunction "2_2") (pintype "passive"))
    )
    (net (code "142") (name "SRV7") (class "Default")
      (node (ref "G1") (pin "PF1-PH1") (pinfunction "PF1-PH1_PF1-PH1") (pintype "bidirectional"))
      (node (ref "JP1") (pin "2") (pinfunction "2_2") (pintype "passive"))
      (node (ref "R7") (pin "2") (pinfunction "2_2") (pintype "passive"))
    )
    (net (code "143") (name "SRV8") (class "Default")
      (node (ref "G1") (pin "PD2") (pinfunction "PD2_PD2") (pintype "bidirectional"))
      (node (ref "JP1") (pin "1") (pinfunction "1_1") (pintype "passive"))
      (node (ref "R6") (pin "2") (pinfunction "2_2") (pintype "passive"))
    )
    (net (code "144") (name "TDRV1") (class "Default")
      (node (ref "G1") (pin "PB12") (pinfunction "PB12_PB12") (pintype "bidirectional"))
      (node (ref "U10") (pin "2") (pinfunction "I_2") (pintype "input"))
      (node (ref "U9") (pin "12") (pinfunction "+IN_12") (pintype "input"))
    )
    (net (code "145") (name "TDRV2") (class "Default")
      (node (ref "G1") (pin "PB2") (pinfunction "PB2_PB2") (pintype "bidirectional"))
      (node (ref "U10") (pin "4") (pinfunction "I_4") (pintype "input"))
      (node (ref "U9") (pin "3") (pinfunction "+IN_3") (pintype "input"))
    )
    (net (code "146") (name "TDRV3") (class "Default")
      (node (ref "G1") (pin "PB15") (pinfunction "PB15_PB15") (pintype "bidirectional"))
      (node (ref "U8") (pin "4") (pinfunction "I_4") (pintype "input"))
      (node (ref "U9") (pin "10") (pinfunction "+IN_10") (pintype "input"))
    )
    (net (code "147") (name "TDRV4") (class "Default")
      (node (ref "G1") (pin "PB1") (pinfunction "PB1_PB1") (pintype "bidirectional"))
      (node (ref "U8") (pin "2") (pinfunction "I_2") (pintype "input"))
      (node (ref "U9") (pin "5") (pinfunction "+IN_5") (pintype "input"))
    )
    (net (code "148") (name "TDRV5") (class "Default")
      (node (ref "G1") (pin "PA0") (pinfunction "PA0_PA0") (pintype "bidirectional"))
      (node (ref "U6") (pin "12") (pinfunction "+IN_12") (pintype "input"))
      (node (ref "U7") (pin "2") (pinfunction "I_2") (pintype "input"))
    )
    (net (code "149") (name "TDRV6") (class "Default")
      (node (ref "G1") (pin "PA4") (pinfunction "PA4_PA4") (pintype "bidirectional"))
      (node (ref "U6") (pin "3") (pinfunction "+IN_3") (pintype "input"))
      (node (ref "U7") (pin "4") (pinfunction "I_4") (pintype "input"))
    )
    (net (code "150") (name "TDRV7") (class "Default")
      (node (ref "G1") (pin "PC3") (pinfunction "PC3_PC3") (pintype "bidirectional"))
      (node (ref "U5") (pin "4") (pinfunction "I_4") (pintype "input"))
      (node (ref "U6") (pin "10") (pinfunction "+IN_10") (pintype "input"))
    )
    (net (code "151") (name "TDRV8") (class "Default")
      (node (ref "G1") (pin "PC0") (pinfunction "PC0_PC0") (pintype "bidirectional"))
      (node (ref "U5") (pin "2") (pinfunction "I_2") (pintype "input"))
      (node (ref "U6") (pin "5") (pinfunction "+IN_5") (pintype "input"))
    )
    (net (code "152") (name "V+") (class "Default")
      (node (ref "C6") (pin "+") (pinfunction "+_+") (pintype "passive"))
      (node (ref "C7") (pin "1") (pinfunction "1_1") (pintype "passive"))
      (node (ref "G1") (pin "E5V") (pinfunction "E5V_E5V") (pintype "power_in"))
      (node (ref "IC1") (pin "1") (pinfunction "FB_1") (pintype "input"))
      (node (ref "L1") (pin "1") (pinfunction "1_1") (pintype "passive"))
      (node (ref "U2") (pin "3") (pinfunction "FB_3") (pintype "bidirectional"))
    )
    (net (code "153") (name "unconnected-(G1-PadBOOT0)") (class "Default")
      (node (ref "G1") (pin "BOOT0") (pinfunction "BOOT0_BOOT0") (pintype "bidirectional"))
    )
    (net (code "154") (name "unconnected-(G1-PadIOREF2)") (class "Default")
      (node (ref "G1") (pin "IOREF2") (pinfunction "IOREF2_IOREF2") (pintype "input"))
    )
    (net (code "155") (name "unconnected-(G1-PadNC1-PF7)") (class "Default")
      (node (ref "G1") (pin "NC1-PF7") (pinfunction "NC1-PF7_NC1-PF7") (pintype "bidirectional"))
    )
    (net (code "156") (name "unconnected-(G1-PadNC2-PF6)") (class "Default")
      (node (ref "G1") (pin "NC2-PF6") (pinfunction "NC2-PF6_NC2-PF6") (pintype "bidirectional"))
    )
    (net (code "157") (name "unconnected-(G1-PadNC3)") (class "Default")
      (node (ref "G1") (pin "NC3") (pinfunction "NC3_NC3") (pintype "no_connect"))
    )
    (net (code "158") (name "unconnected-(G1-PadNC4)") (class "Default")
      (node (ref "G1") (pin "NC4") (pinfunction "NC4_NC4") (pintype "no_connect"))
    )
    (net (code "159") (name "unconnected-(G1-PadNC5-PD8)") (class "Default")
      (node (ref "G1") (pin "NC5-PD8") (pinfunction "NC5-PD8_NC5-PD8") (pintype "bidirectional"))
    )
    (net (code "160") (name "unconnected-(G1-PadNC6-PB11)") (class "Default")
      (node (ref "G1") (pin "NC6-PB11") (pinfunction "NC6-PB11_NC6-PB11") (pintype "no_connect"))
    )
    (net (code "161") (name "unconnected-(G1-PadNC7-PF5)") (class "Default")
      (node (ref "G1") (pin "NC7-PF5") (pinfunction "NC7-PF5_NC7-PF5") (pintype "bidirectional"))
    )
    (net (code "162") (name "unconnected-(G1-PadNC8-PF4)") (class "Default")
      (node (ref "G1") (pin "NC8-PF4") (pinfunction "NC8-PF4_NC8-PF4") (pintype "bidirectional"))
    )
    (net (code "163") (name "unconnected-(G1-PadNRESET)") (class "Default")
      (node (ref "G1") (pin "NRESET") (pinfunction "NRESET_NRESET") (pintype "input"))
    )
    (net (code "164") (name "unconnected-(G1-PadPA1)") (class "Default")
      (node (ref "G1") (pin "PA1") (pinfunction "PA1_PA1") (pintype "bidirectional"))
    )
    (net (code "165") (name "unconnected-(G1-PadPA2)") (class "Default")
      (node (ref "G1") (pin "PA2") (pinfunction "PA2_PA2") (pintype "bidirectional"))
    )
    (net (code "166") (name "unconnected-(G1-PadPA3)") (class "Default")
      (node (ref "G1") (pin "PA3") (pinfunction "PA3_PA3") (pintype "bidirectional"))
    )
    (net (code "167") (name "unconnected-(G1-PadPA5)") (class "Default")
      (node (ref "G1") (pin "PA5") (pinfunction "PA5_PA5") (pintype "bidirectional"))
    )
    (net (code "168") (name "unconnected-(G1-PadPA7)") (class "Default")
      (node (ref "G1") (pin "PA7") (pinfunction "PA7_PA7") (pintype "bidirectional"))
    )
    (net (code "169") (name "unconnected-(G1-PadPA9)") (class "Default")
      (node (ref "G1") (pin "PA9") (pinfunction "PA9_PA9") (pintype "bidirectional"))
    )
    (net (code "170") (name "unconnected-(G1-PadPA10)") (class "Default")
      (node (ref "G1") (pin "PA10") (pinfunction "PA10_PA10") (pintype "bidirectional"))
    )
    (net (code "171") (name "unconnected-(G1-PadPA11)") (class "Default")
      (node (ref "G1") (pin "PA11") (pinfunction "PA11_PA11") (pintype "bidirectional"))
    )
    (net (code "172") (name "unconnected-(G1-PadPA12)") (class "Default")
      (node (ref "G1") (pin "PA12") (pinfunction "PA12_PA12") (pintype "bidirectional"))
    )
    (net (code "173") (name "unconnected-(G1-PadPA13)") (class "Default")
      (node (ref "G1") (pin "PA13") (pinfunction "PA13_PA13") (pintype "bidirectional"))
    )
    (net (code "174") (name "unconnected-(G1-PadPA14)") (class "Default")
      (node (ref "G1") (pin "PA14") (pinfunction "PA14_PA14") (pintype "bidirectional"))
    )
    (net (code "175") (name "unconnected-(G1-PadPB0)") (class "Default")
      (node (ref "G1") (pin "PB0") (pinfunction "PB0_PB0") (pintype "bidirectional"))
    )
    (net (code "176") (name "unconnected-(G1-PadPC1)") (class "Default")
      (node (ref "G1") (pin "PC1") (pinfunction "PC1_PC1") (pintype "bidirectional"))
    )
    (net (code "177") (name "unconnected-(G1-PadPC4)") (class "Default")
      (node (ref "G1") (pin "PC4") (pinfunction "PC4_PC4") (pintype "bidirectional"))
    )
    (net (code "178") (name "unconnected-(G1-PadPC5)") (class "Default")
      (node (ref "G1") (pin "PC5") (pinfunction "PC5_PC5") (pintype "bidirectional"))
    )
    (net (code "179") (name "unconnected-(G1-PadPC13)") (class "Default")
      (node (ref "G1") (pin "PC13") (pinfunction "PC13_PC13") (pintype "bidirectional"))
    )
    (net (code "180") (name "unconnected-(G1-PadPC14)") (class "Default")
      (node (ref "G1") (pin "PC14") (pinfunction "PC14_PC14") (pintype "bidirectional"))
    )
    (net (code "181") (name "unconnected-(G1-PadPC15)") (class "Default")
      (node (ref "G1") (pin "PC15") (pinfunction "PC15_PC15") (pintype "bidirectional"))
    )
    (net (code "182") (name "unconnected-(G1-PadPF0-PH0)") (class "Default")
      (node (ref "G1") (pin "PF0-PH0") (pinfunction "PF0-PH0_PF0-PH0") (pintype "bidirectional"))
    )
    (net (code "183") (name "unconnected-(H1-MOUNT-PadB3,3)") (class "Default")
      (node (ref "H1") (pin "B3,3") (pinfunction "MOUNT_B3,3") (pintype "passive"))
    )
    (net (code "184") (name "unconnected-(H2-MOUNT-PadB3,3)") (class "Default")
      (node (ref "H2") (pin "B3,3") (pinfunction "MOUNT_B3,3") (pintype "passive"))
    )
    (net (code "185") (name "unconnected-(H3-MOUNT-PadB3,3)") (class "Default")
      (node (ref "H3") (pin "B3,3") (pinfunction "MOUNT_B3,3") (pintype "passive"))
    )
    (net (code "186") (name "unconnected-(H4-MOUNT-PadB3,3)") (class "Default")
      (node (ref "H4") (pin "B3,3") (pinfunction "MOUNT_B3,3") (pintype "passive"))
    )
  )
)
